# Hutschienenmoped-XL_2ETH.net
KiCad netlist of a schematic drawn in EAGLE
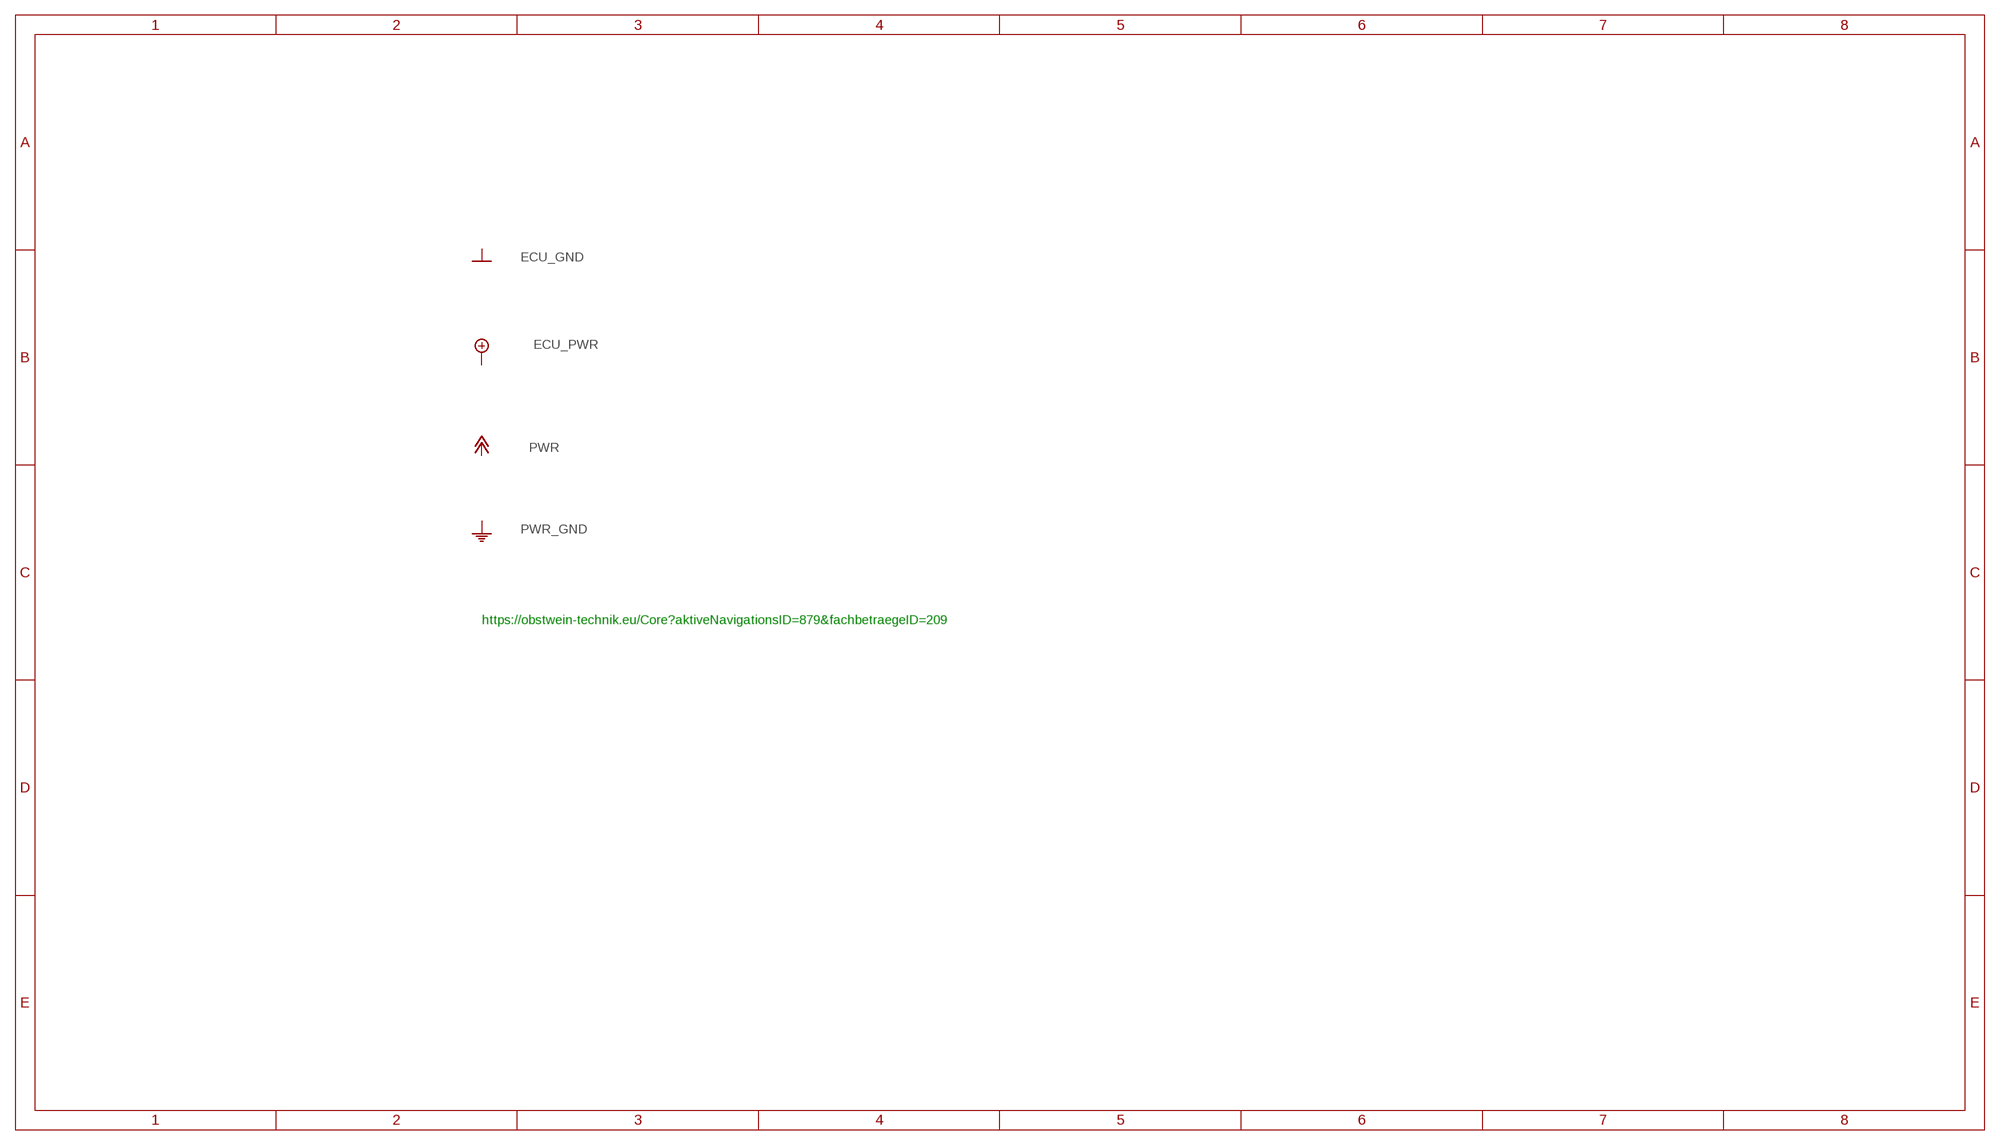
[diagram p0: schematic, sheet 1]
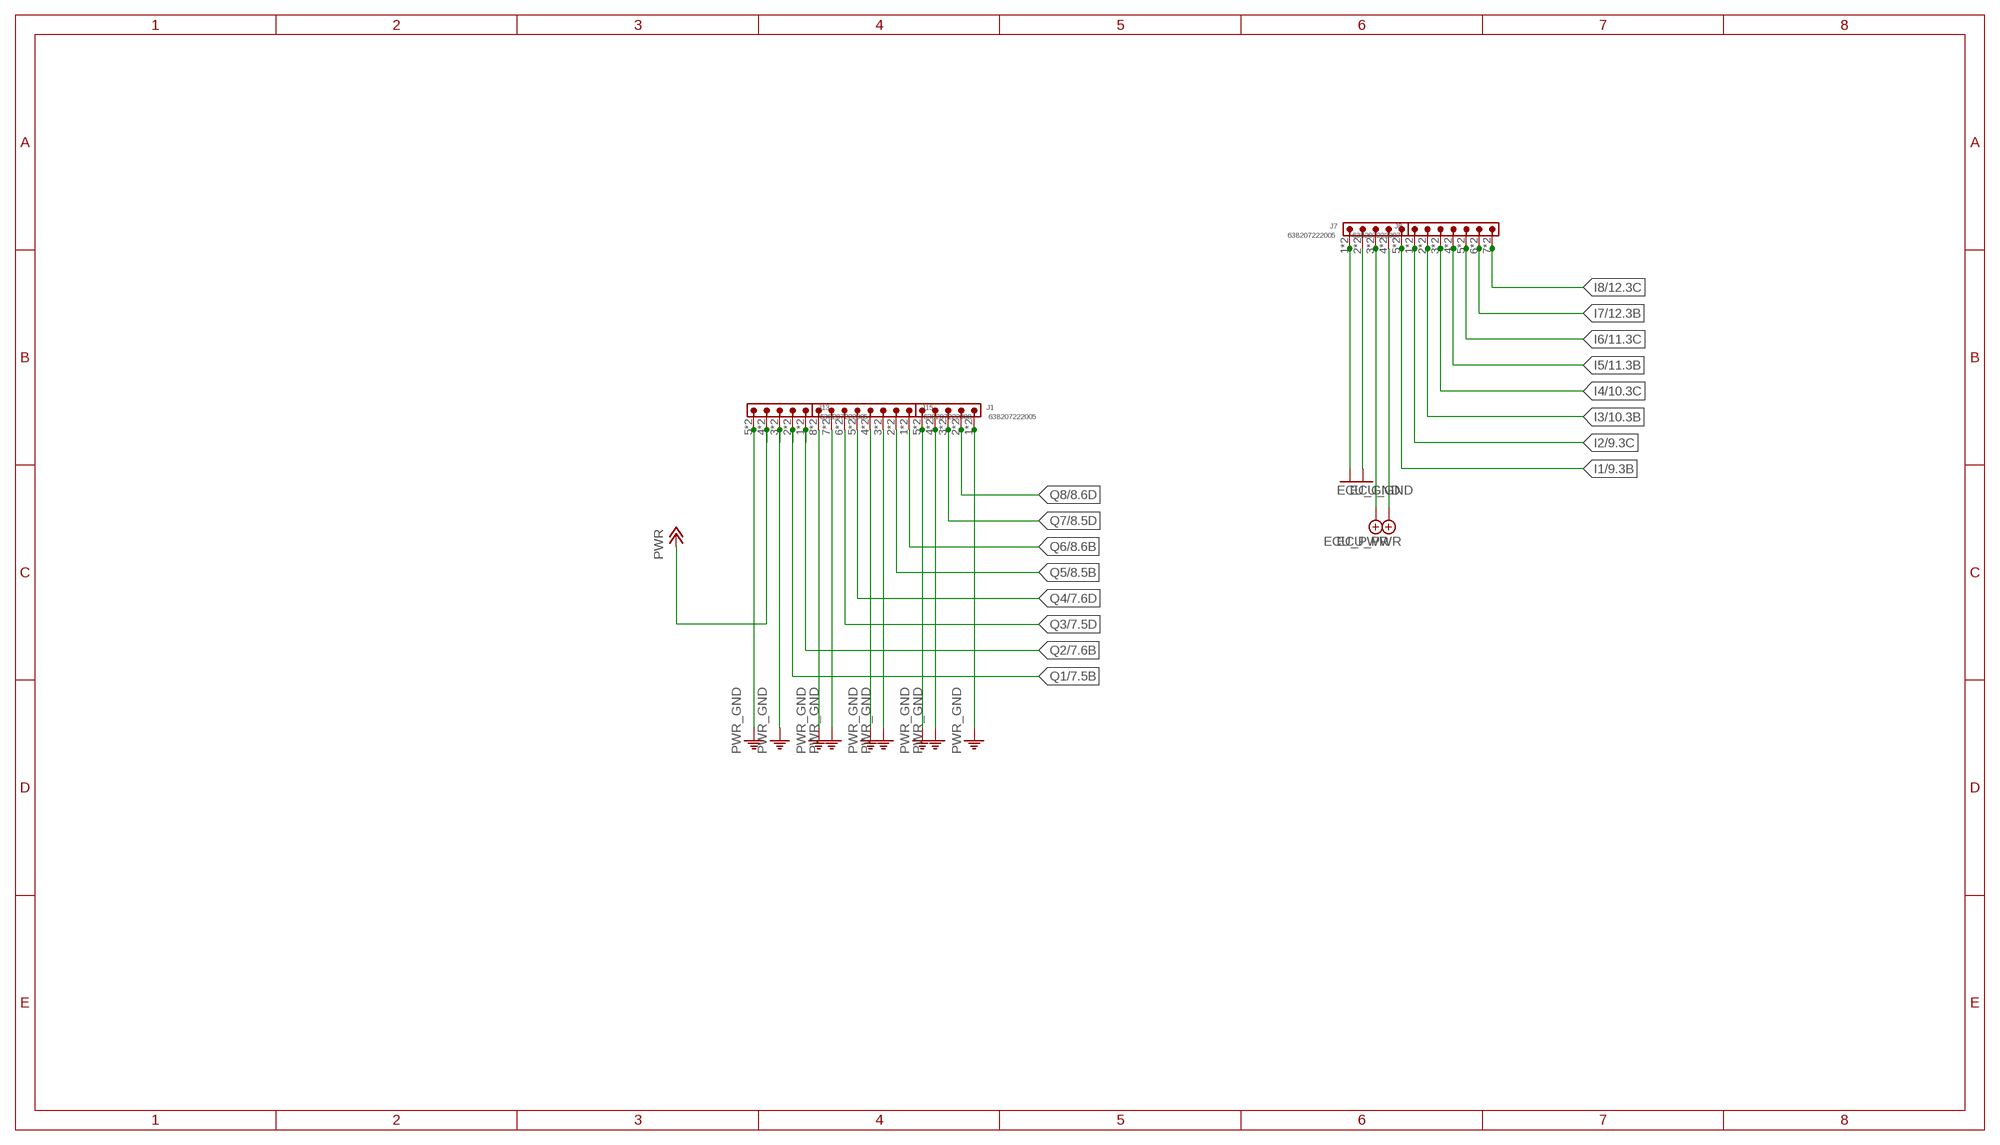
[diagram p1: schematic, sheet 2]
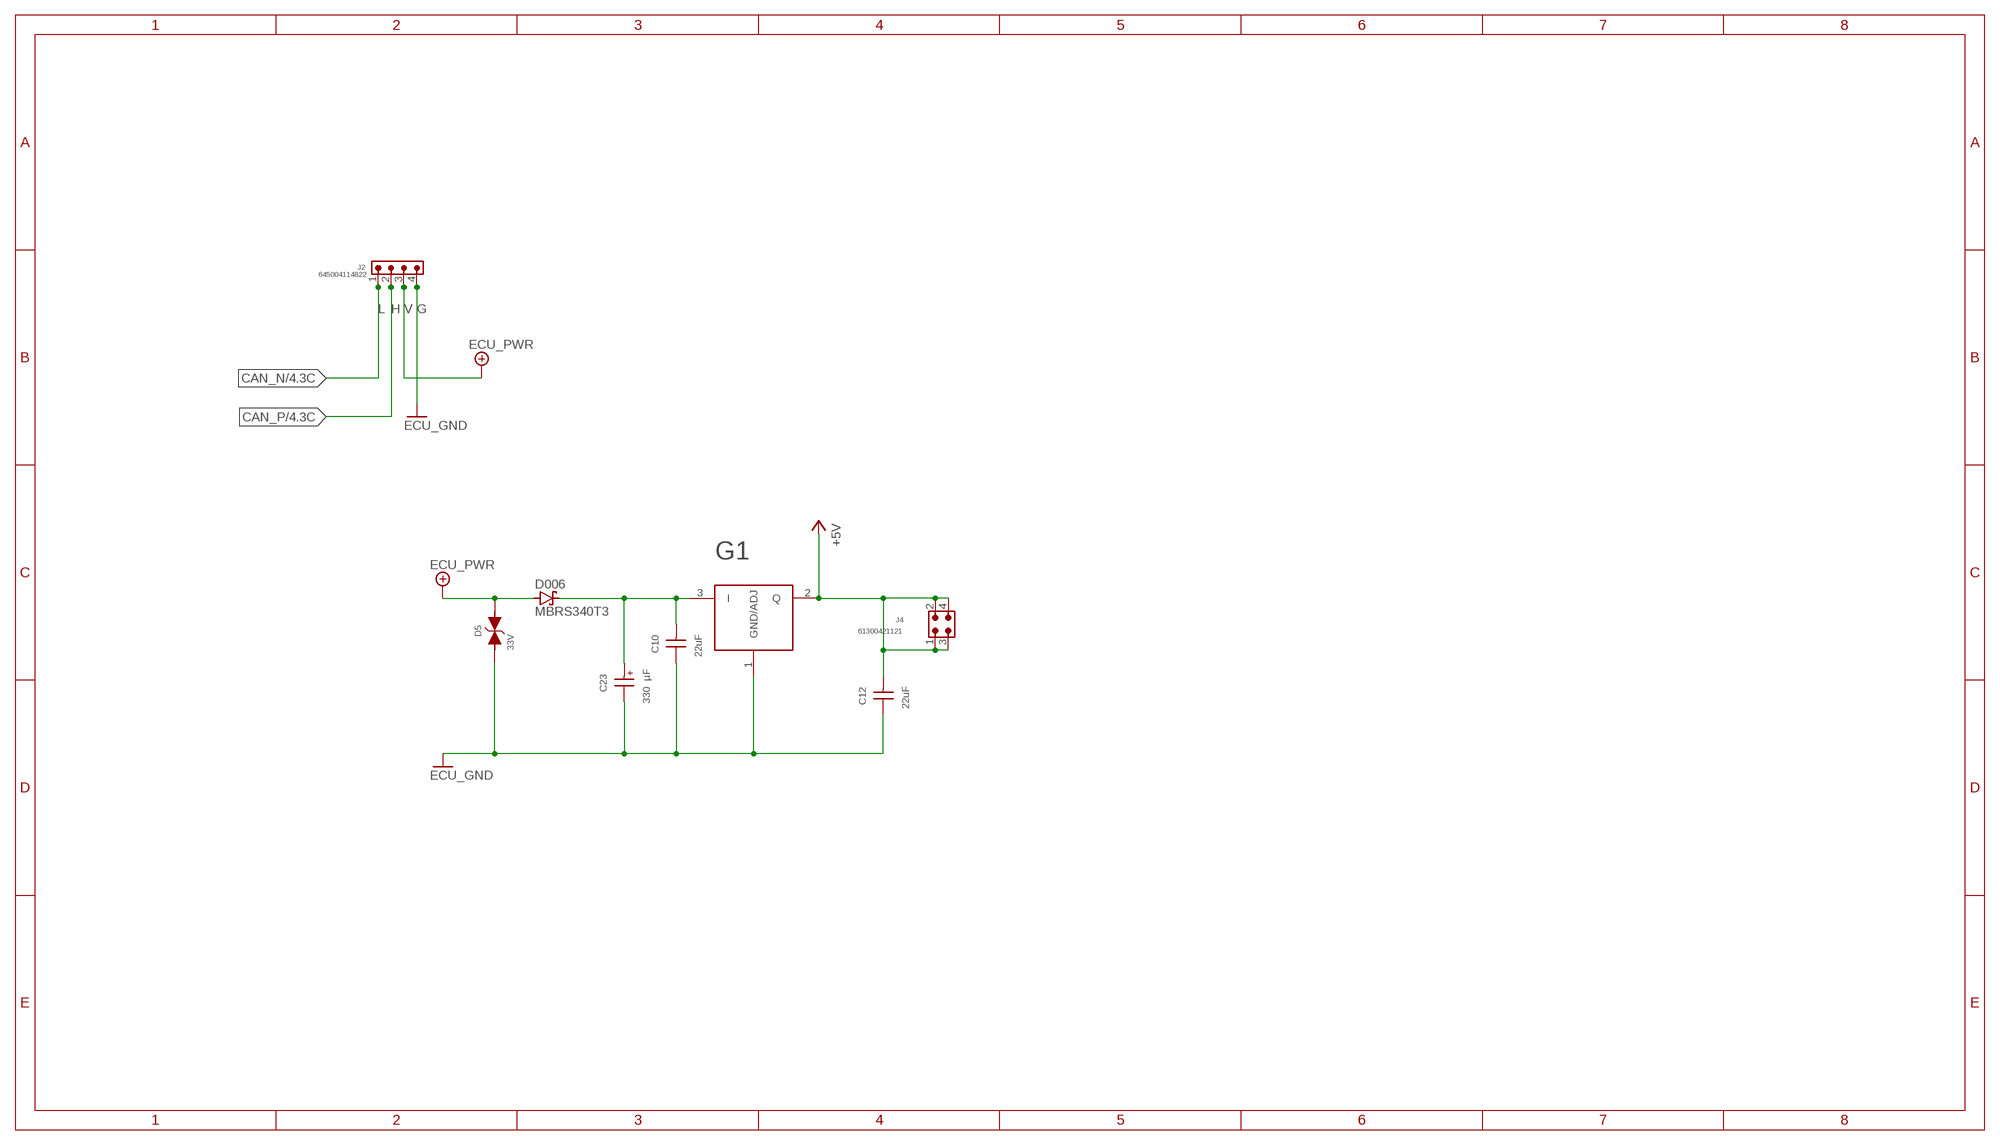
[diagram p2: schematic, sheet 3]
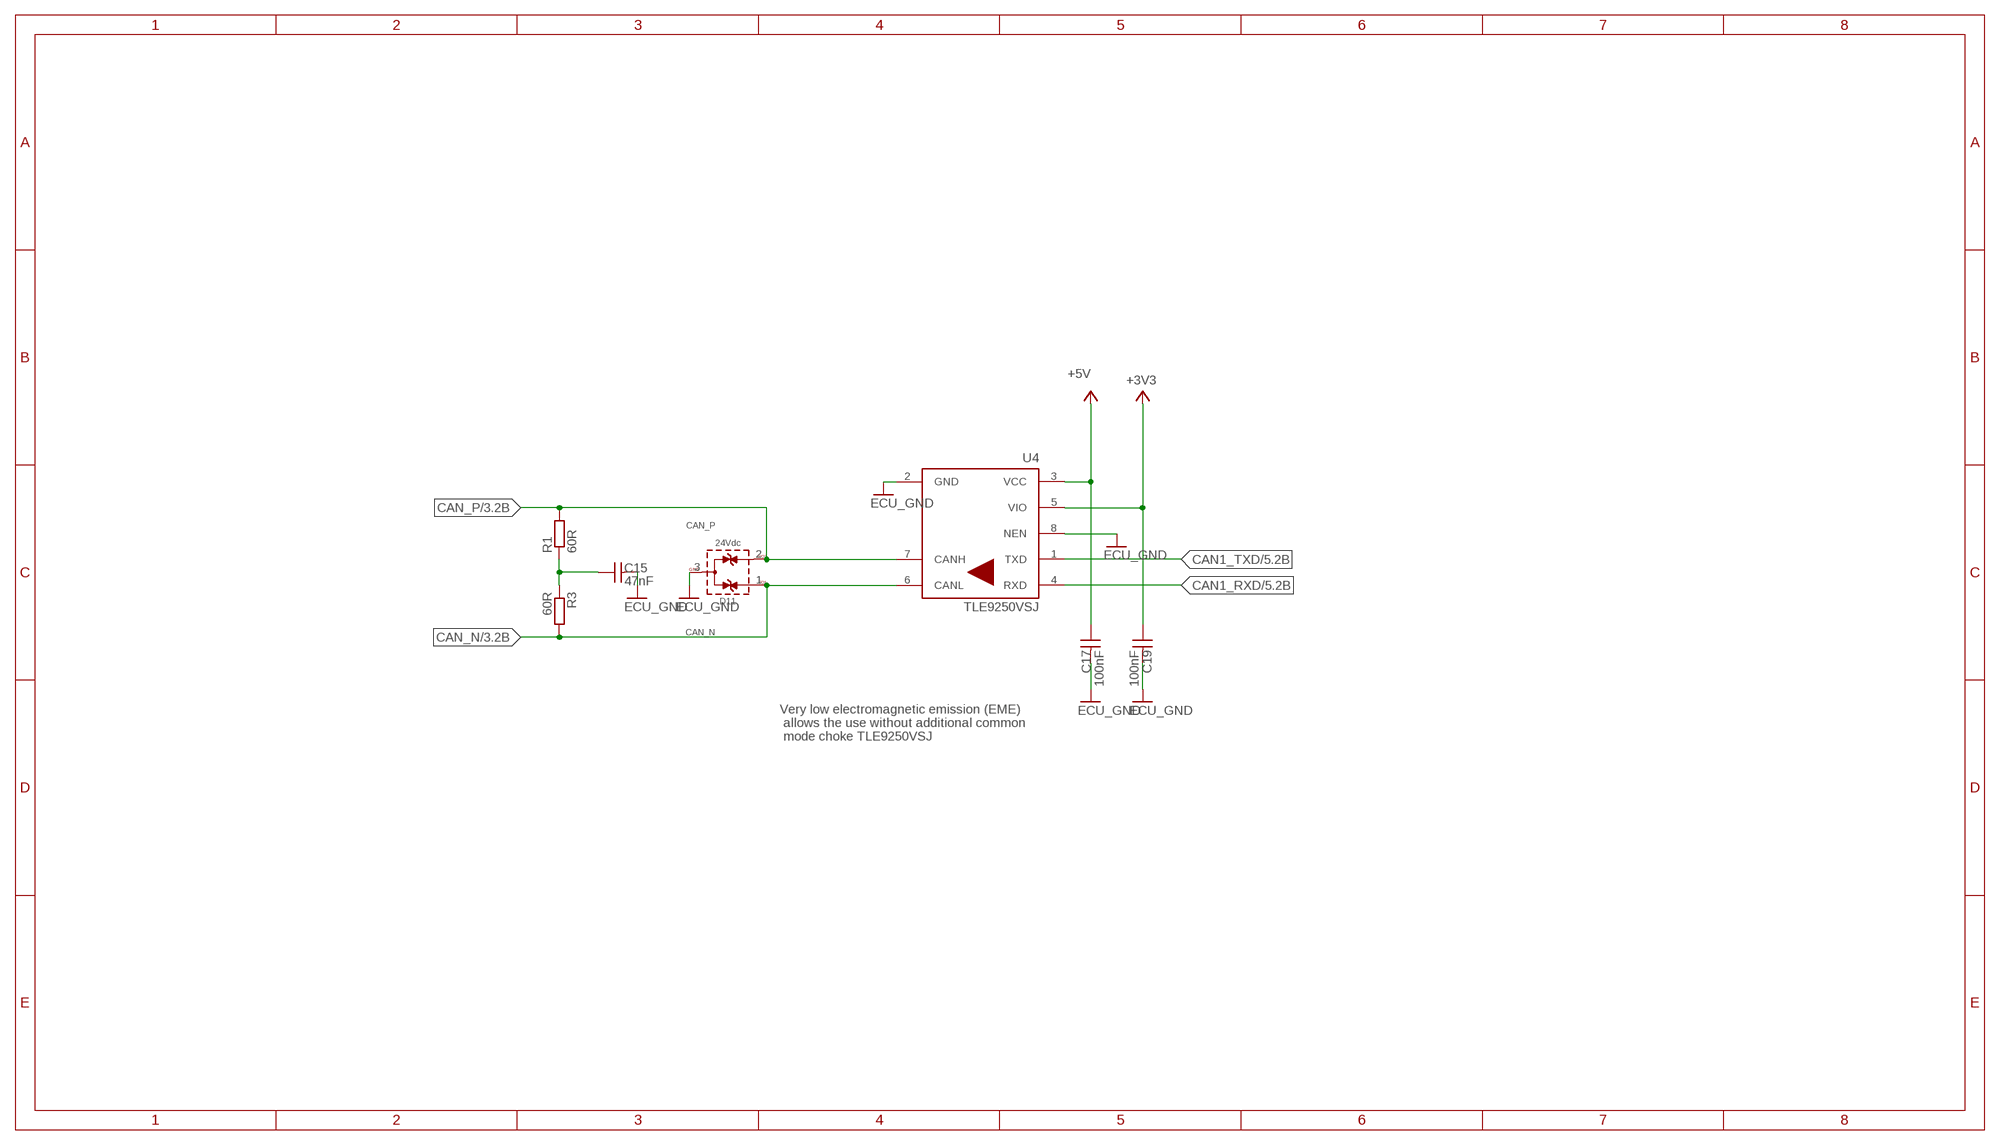
[diagram p3: schematic, sheet 4]
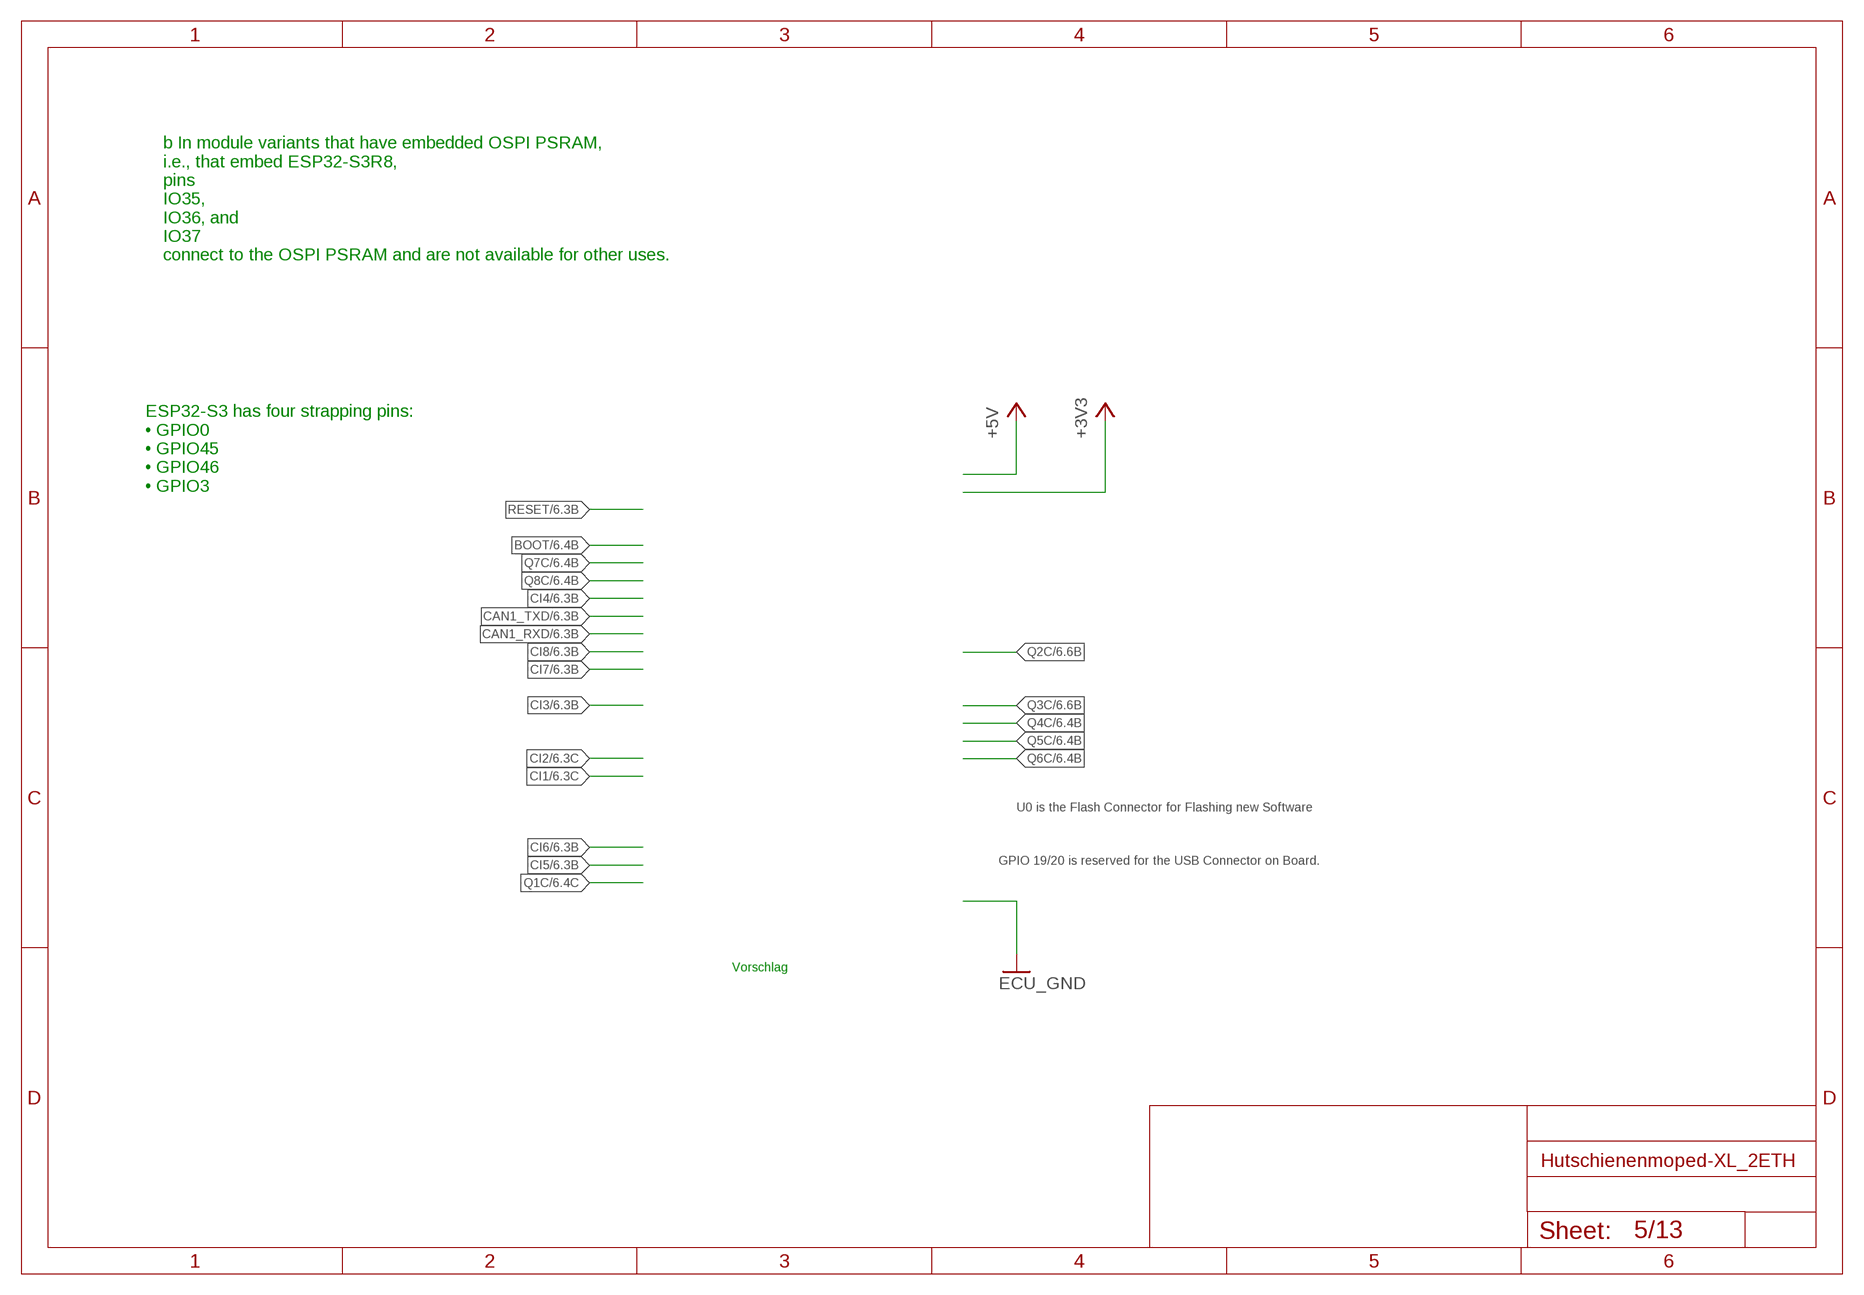
[diagram p4: schematic, sheet 5]
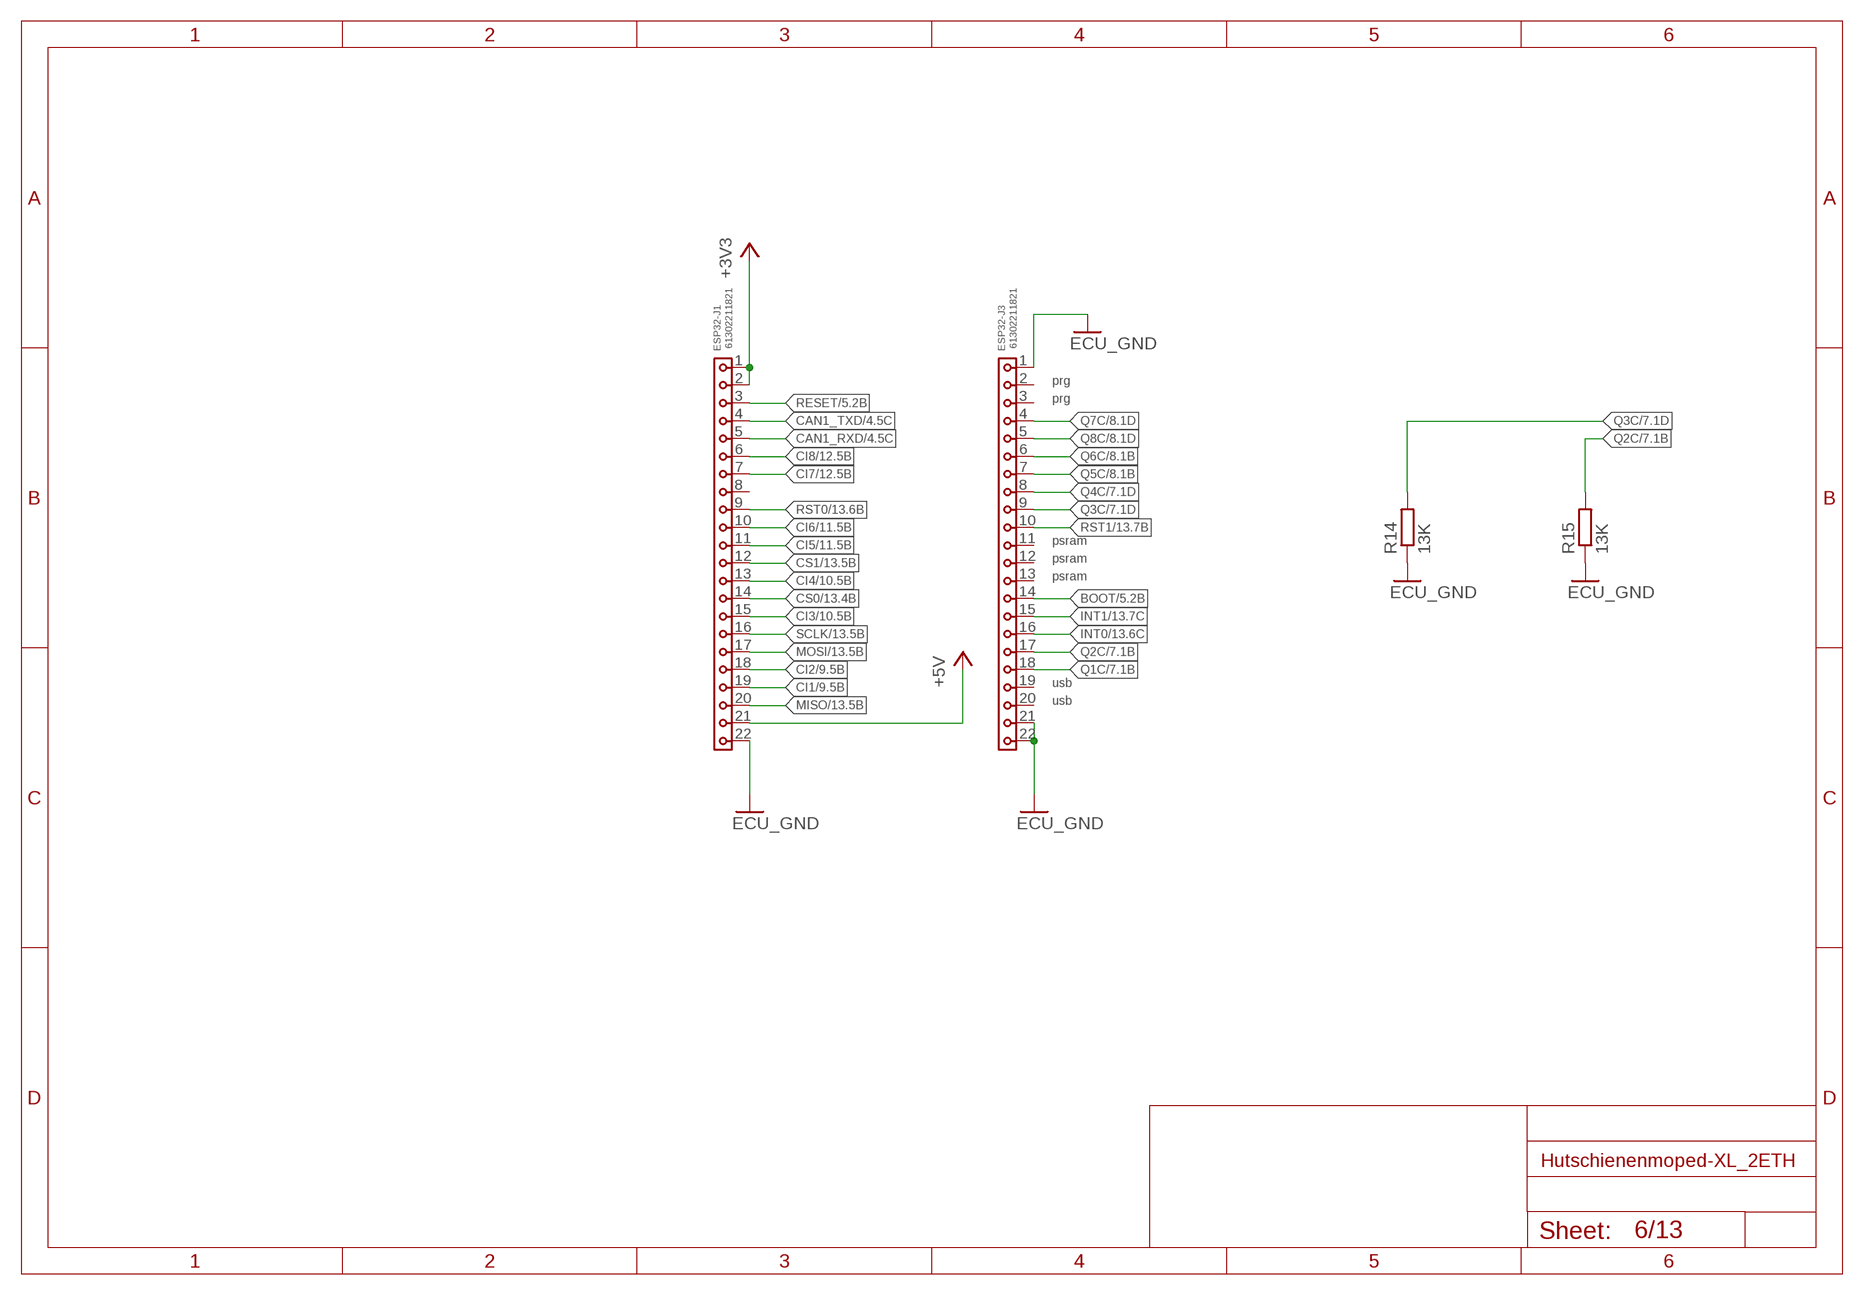
[diagram p5: schematic, sheet 6]
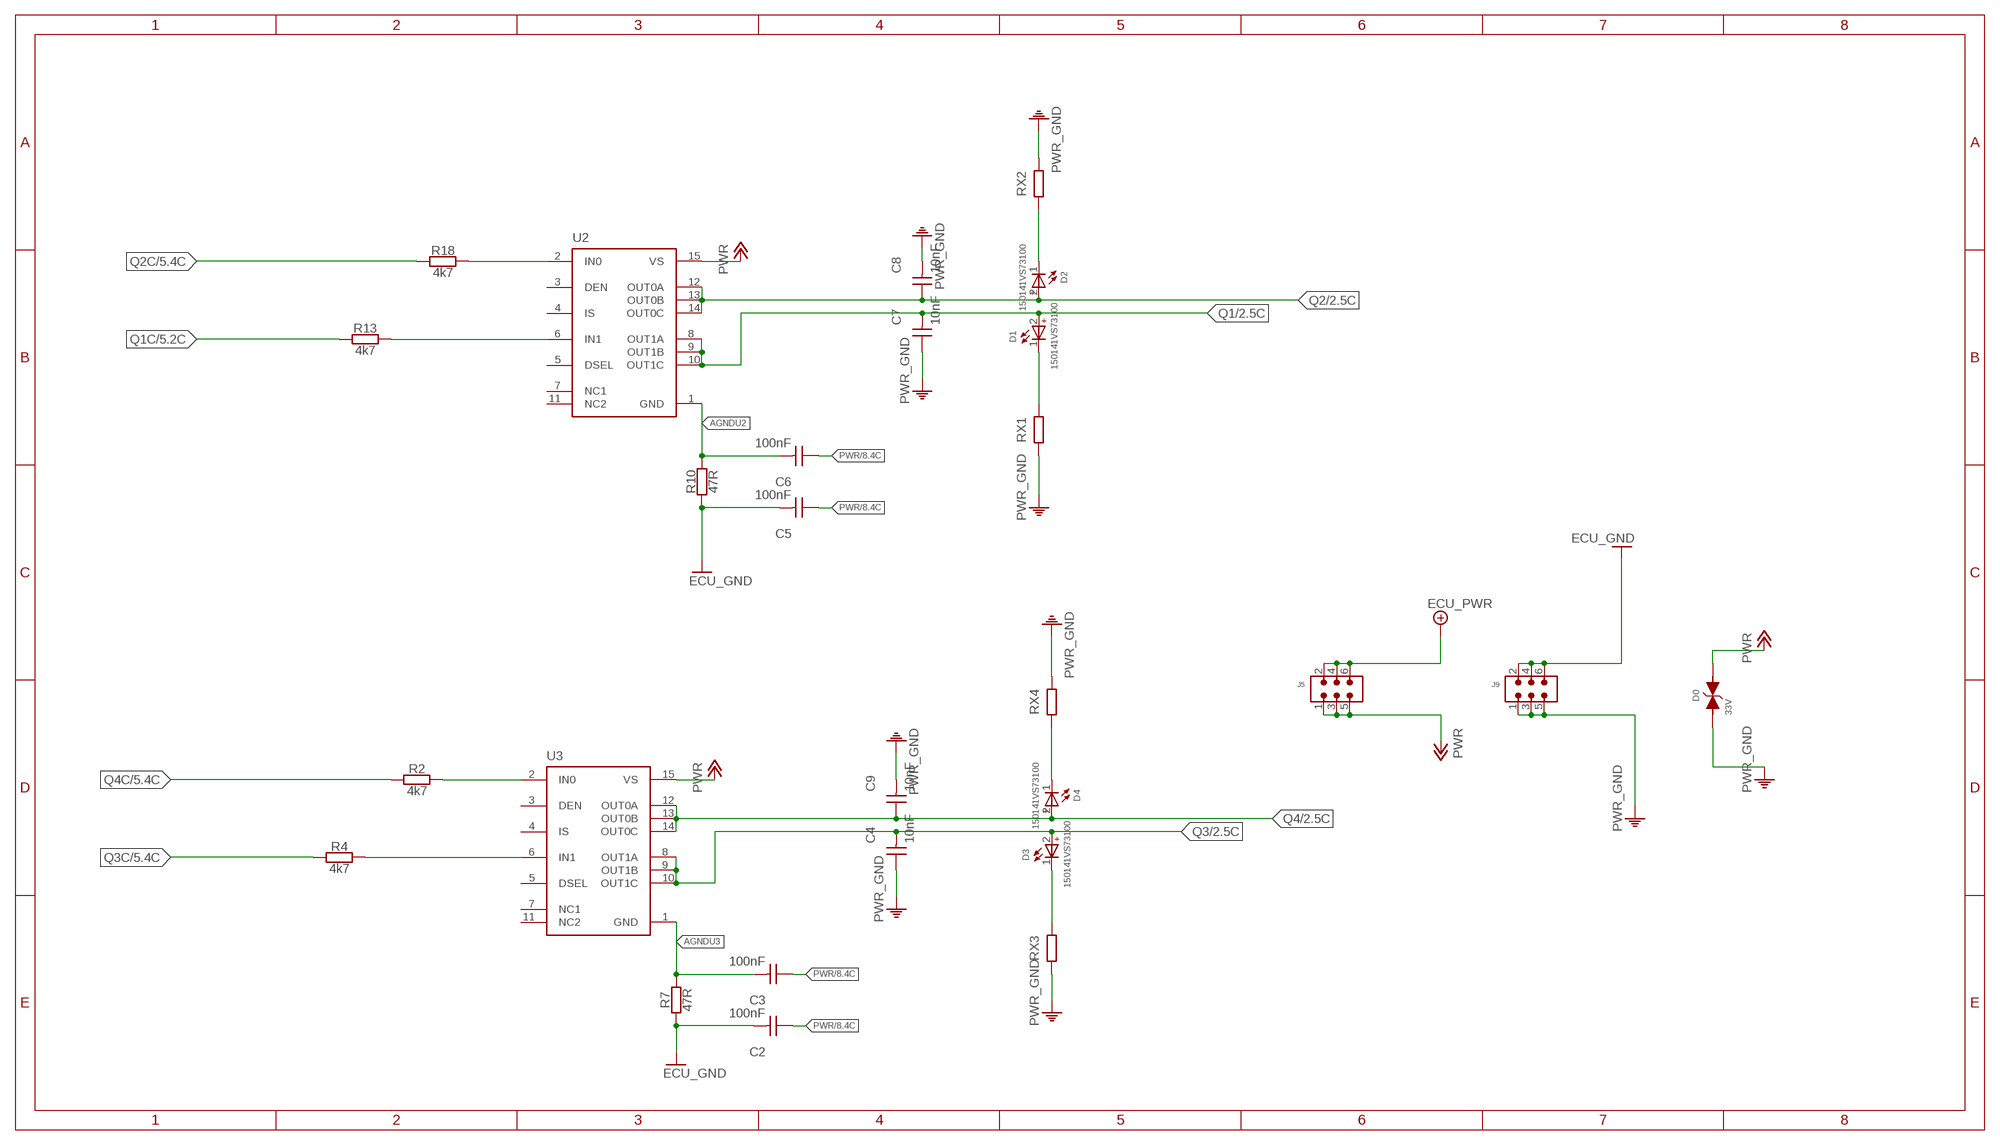
[diagram p6: schematic, sheet 7]
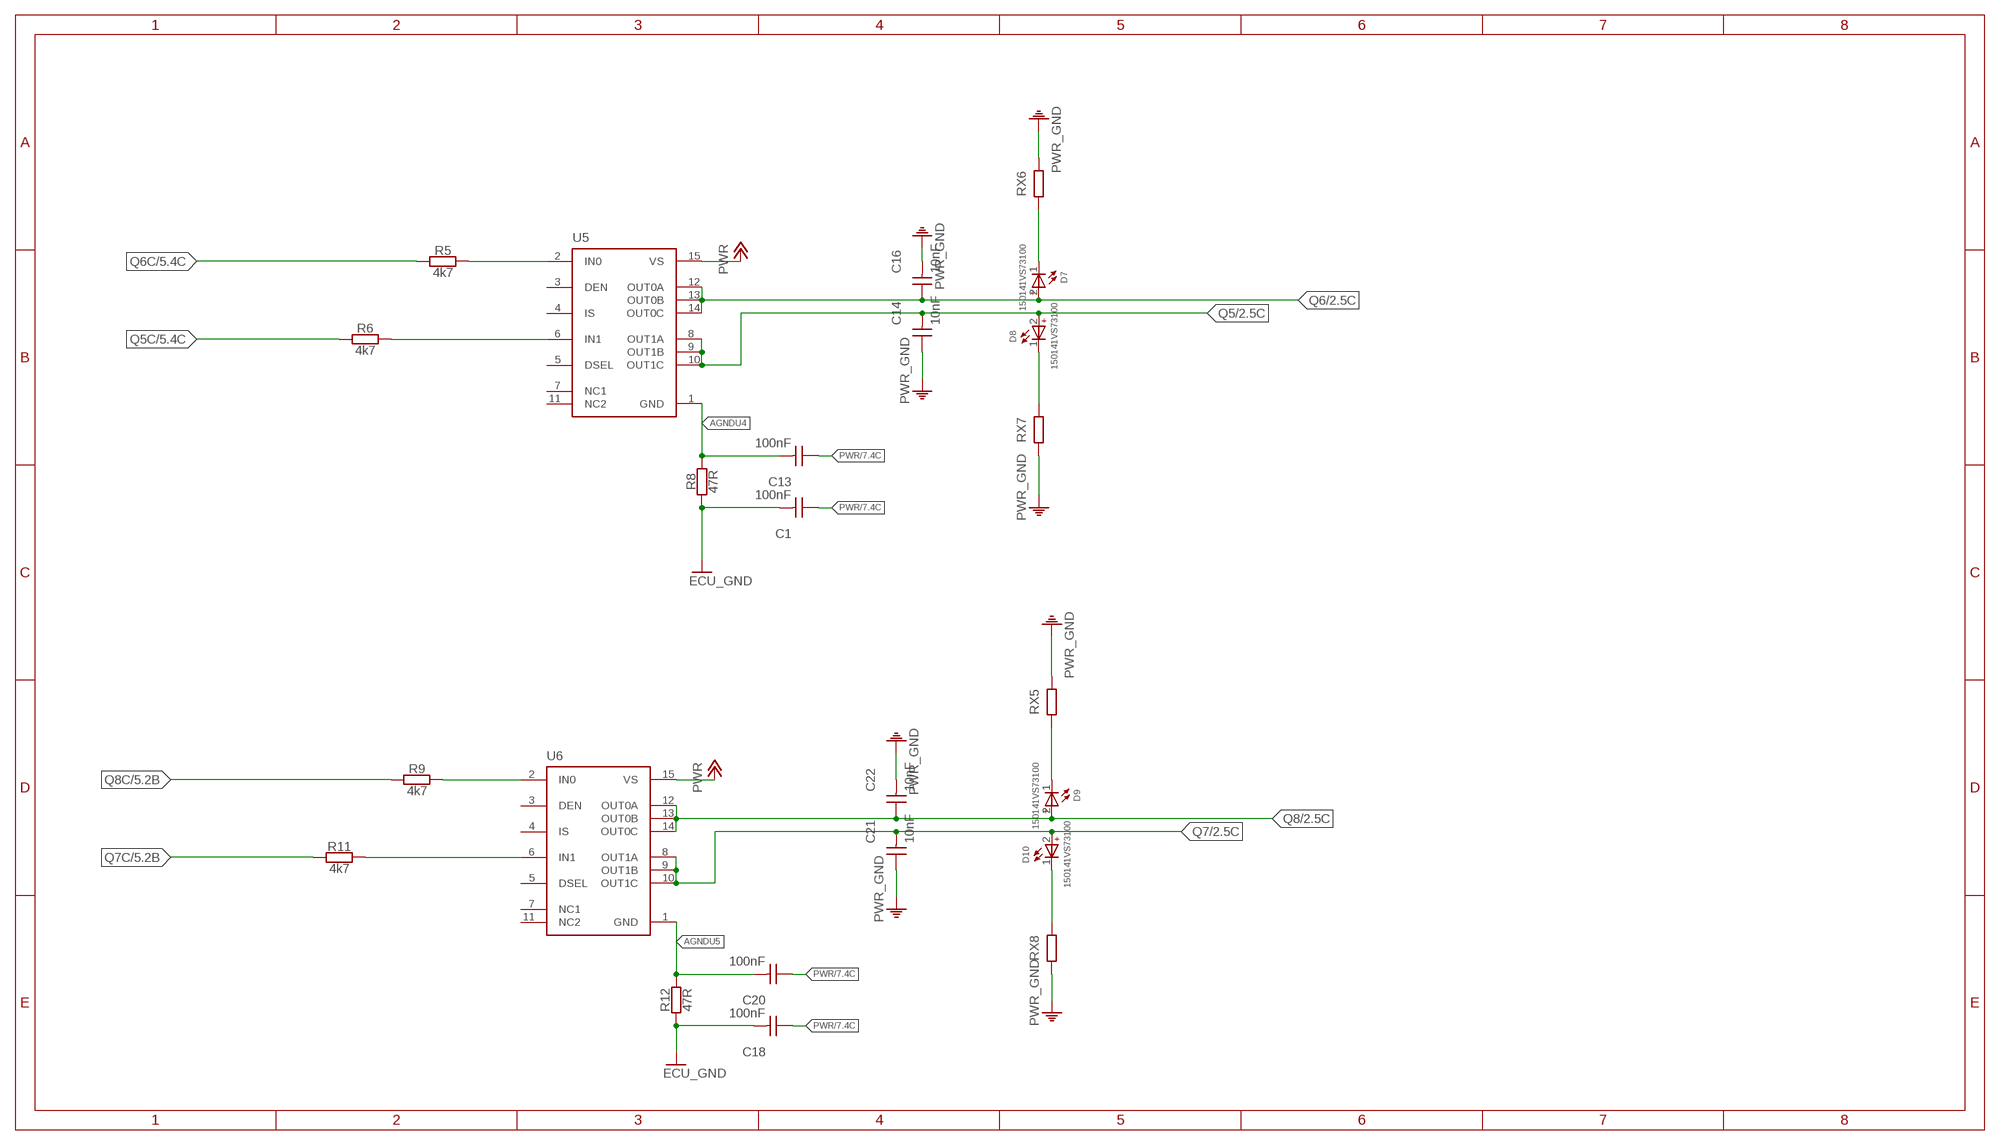
[diagram p7: schematic, sheet 8]
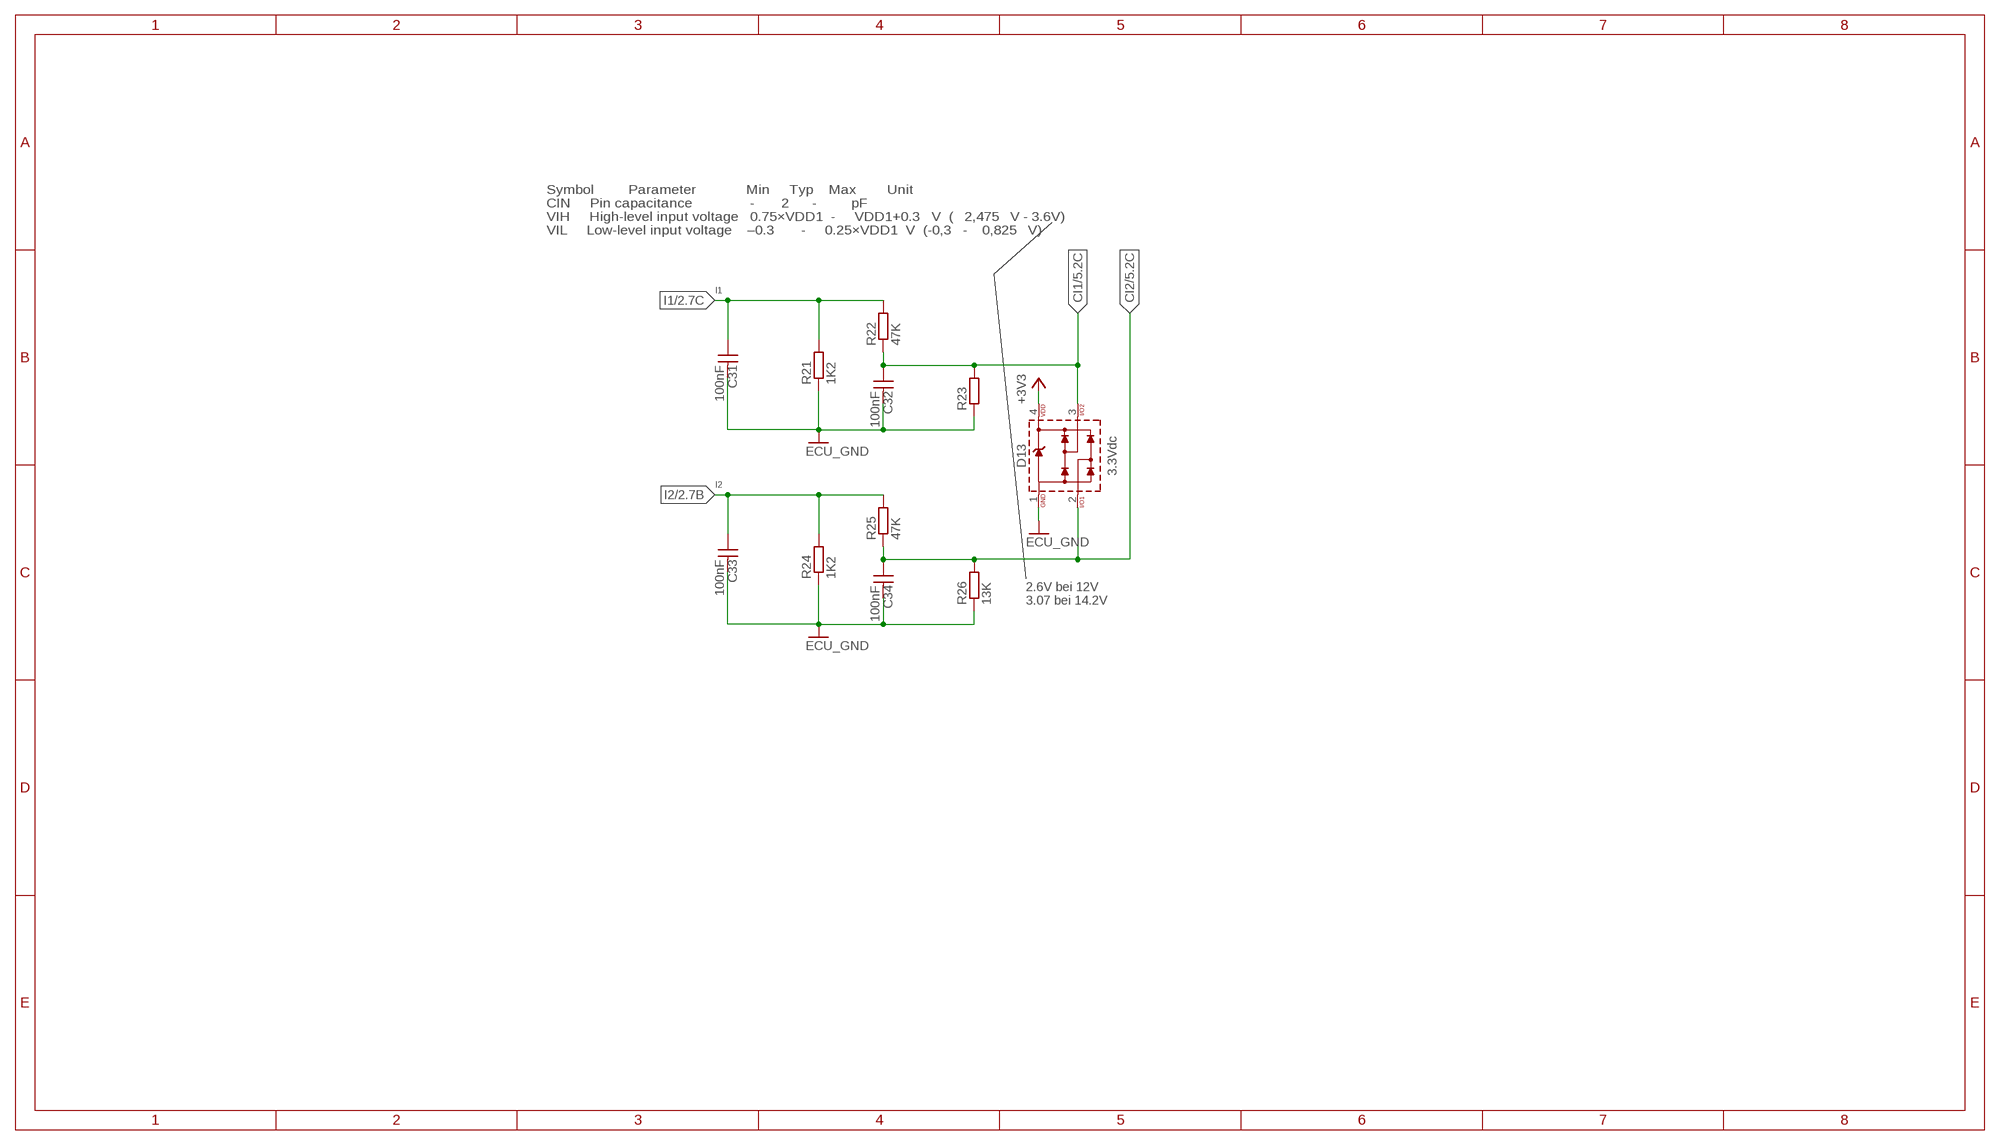
[diagram p8: schematic, sheet 9]
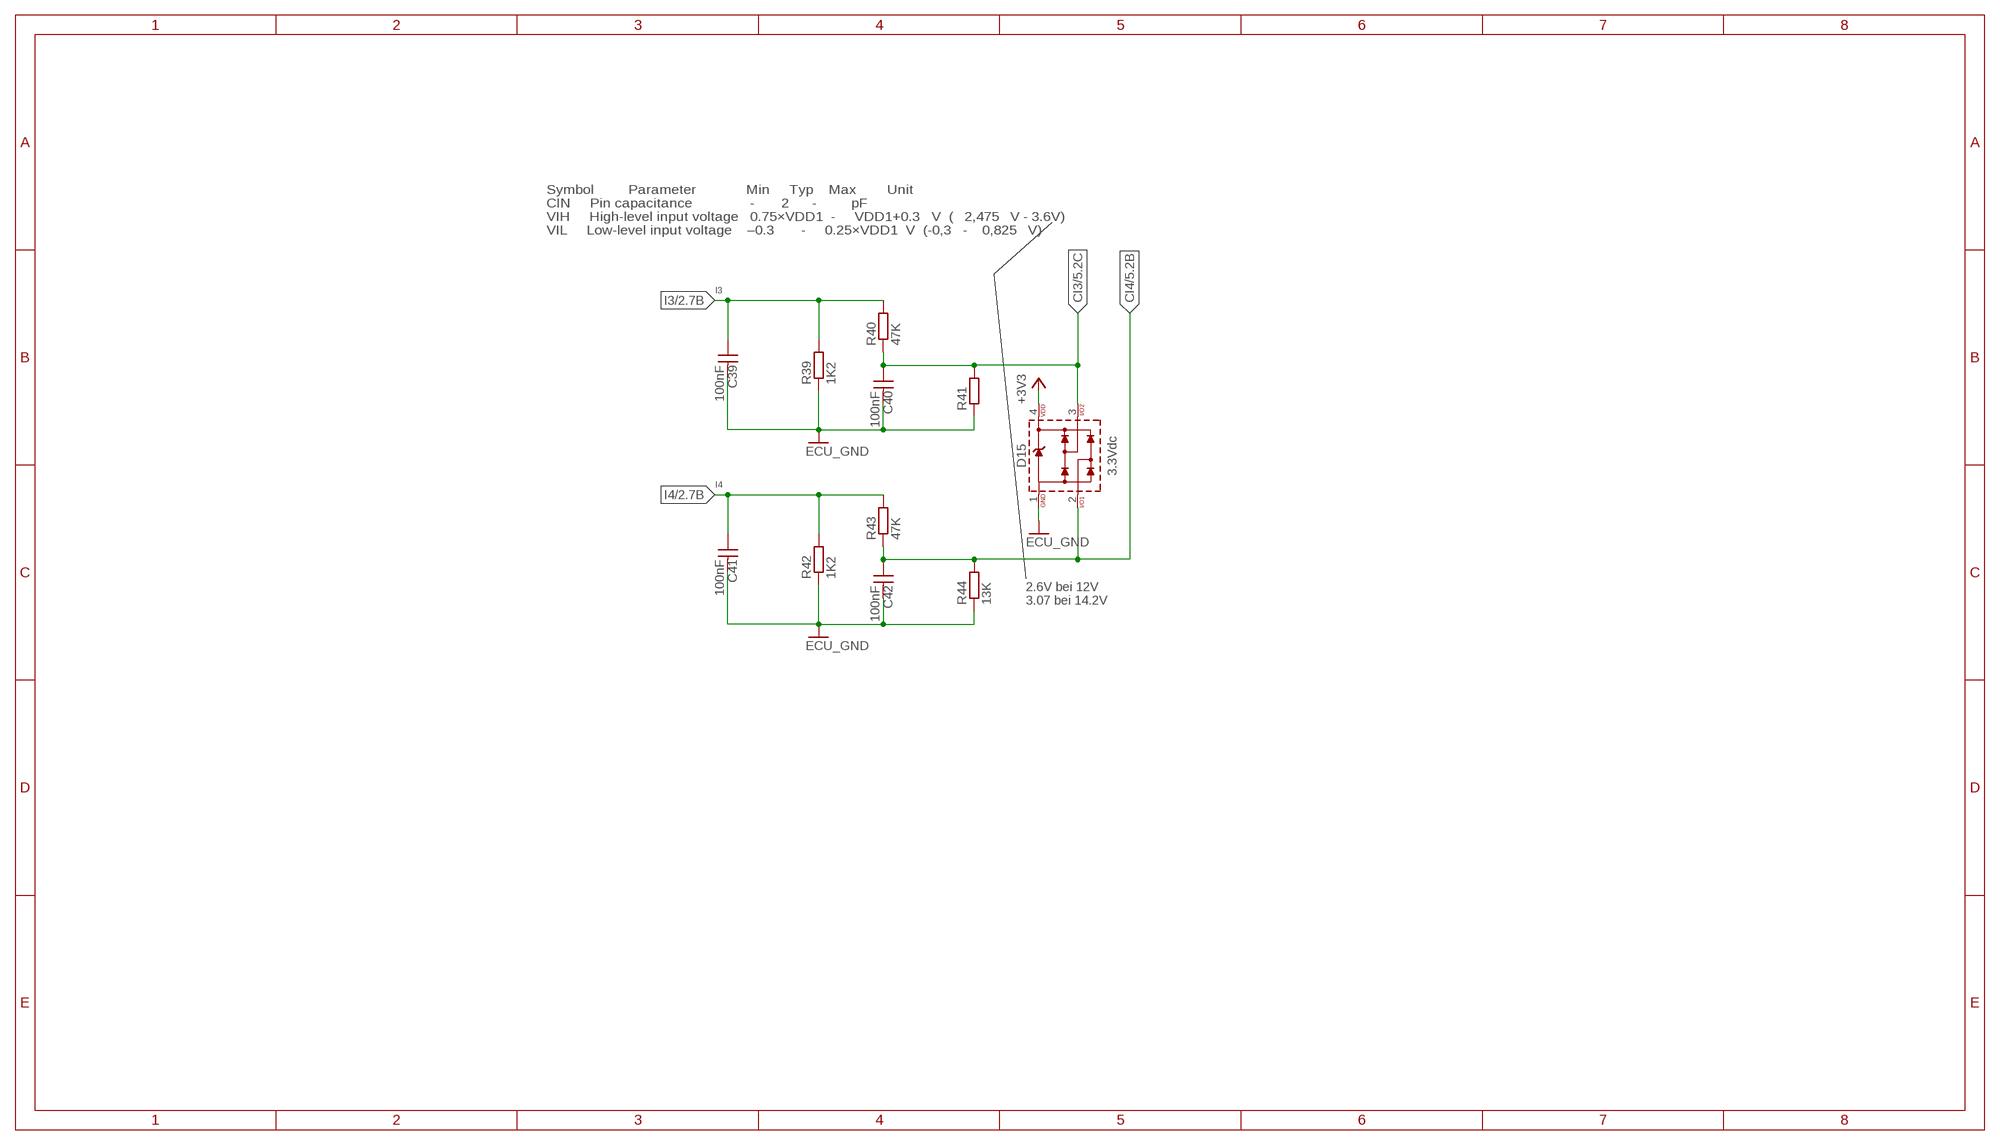
[diagram p9: schematic, sheet 10]
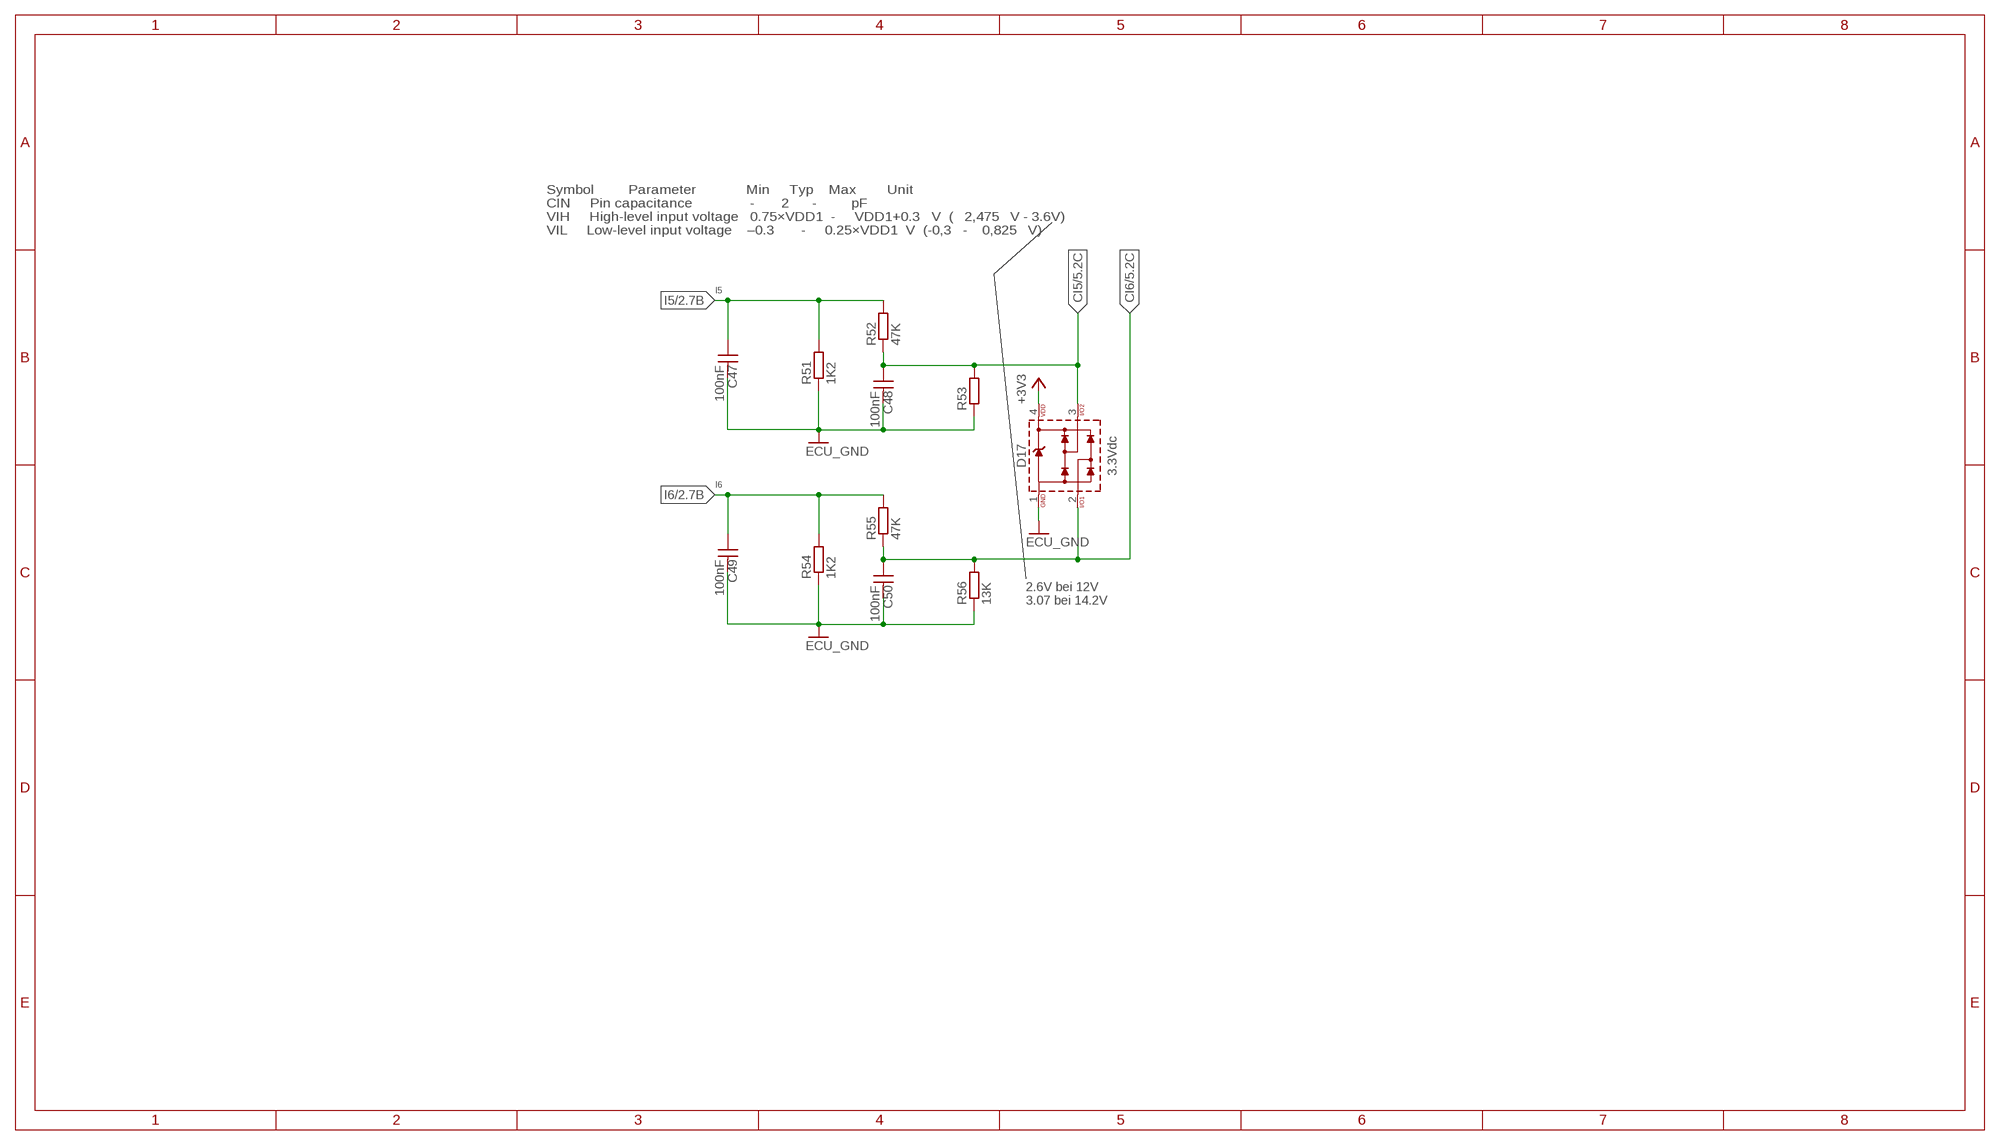
[diagram p10: schematic, sheet 11]
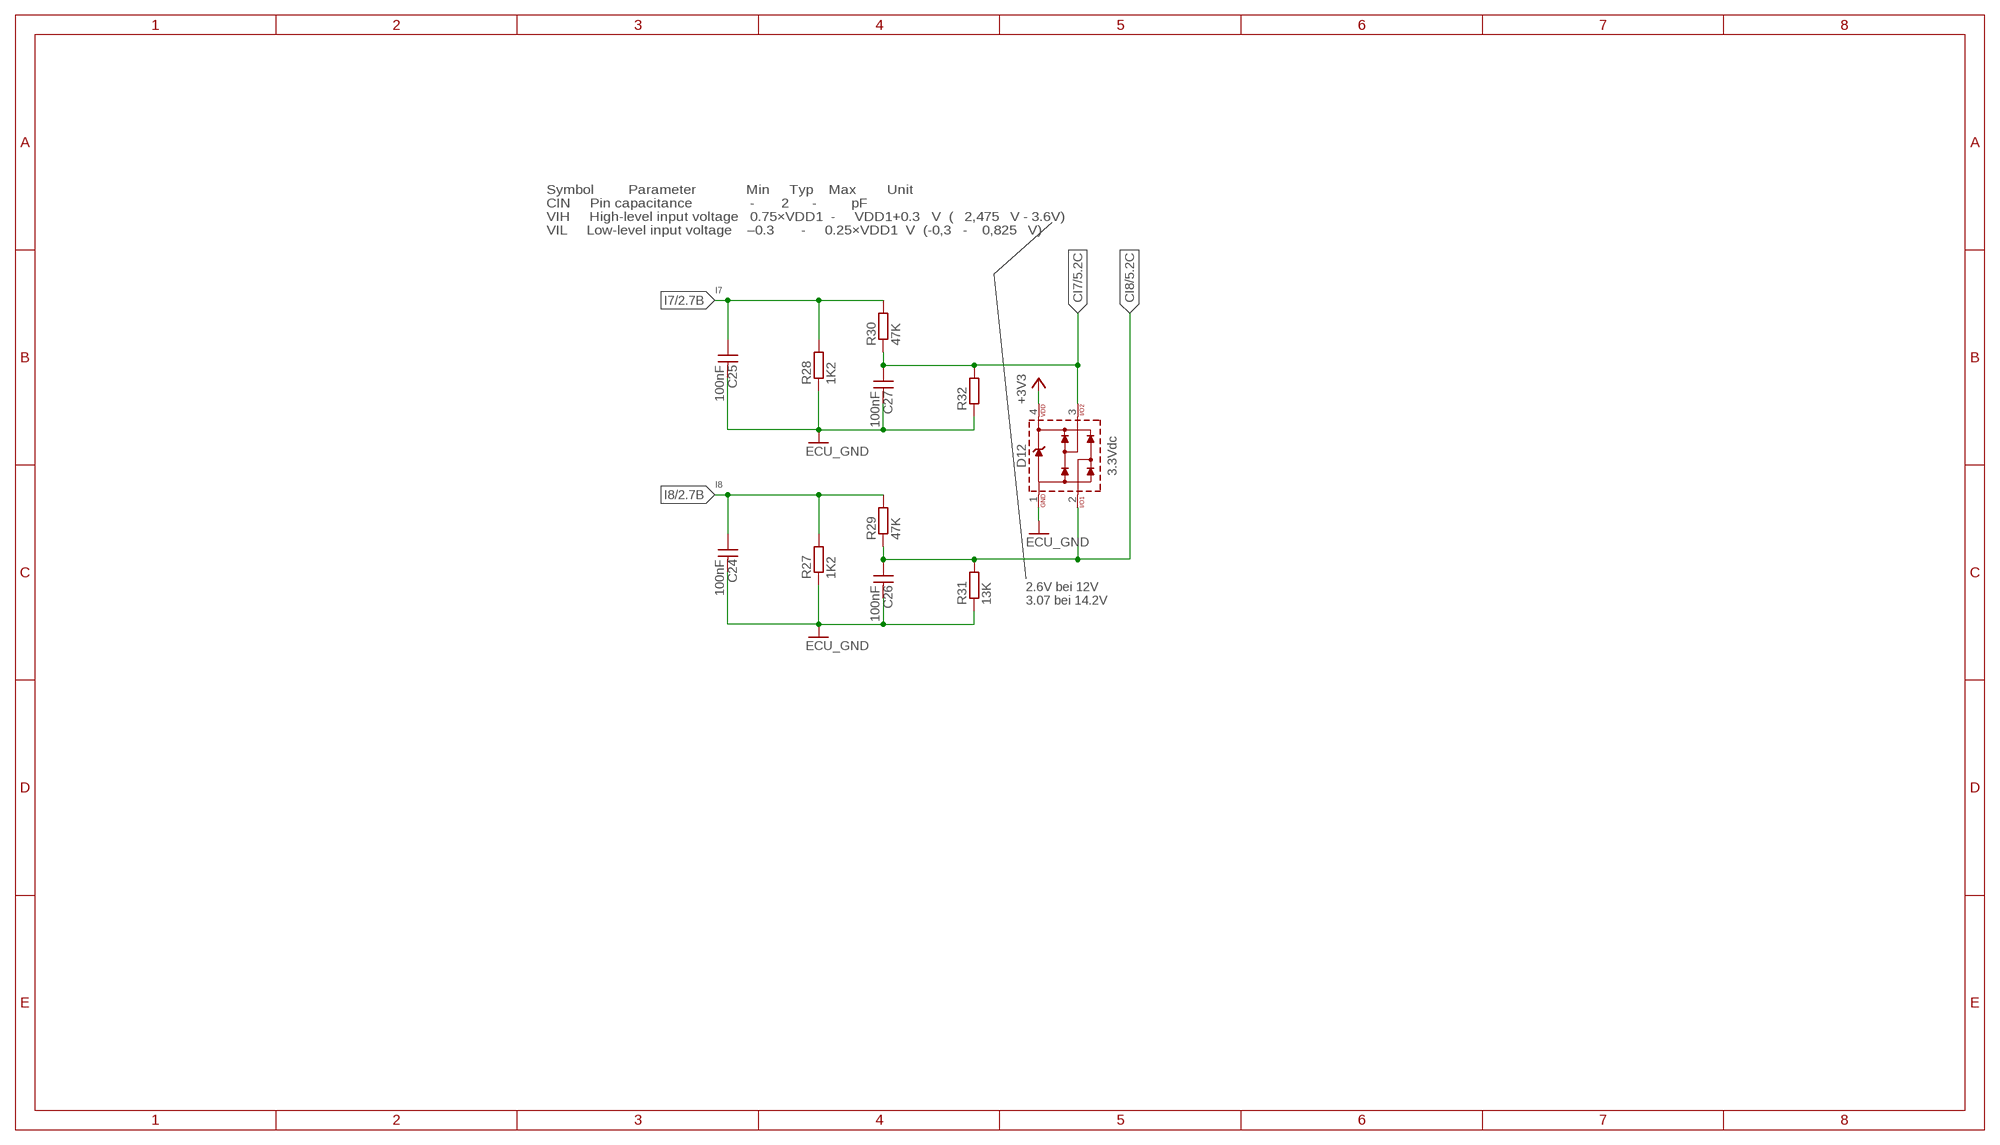
[diagram p11: schematic, sheet 12]
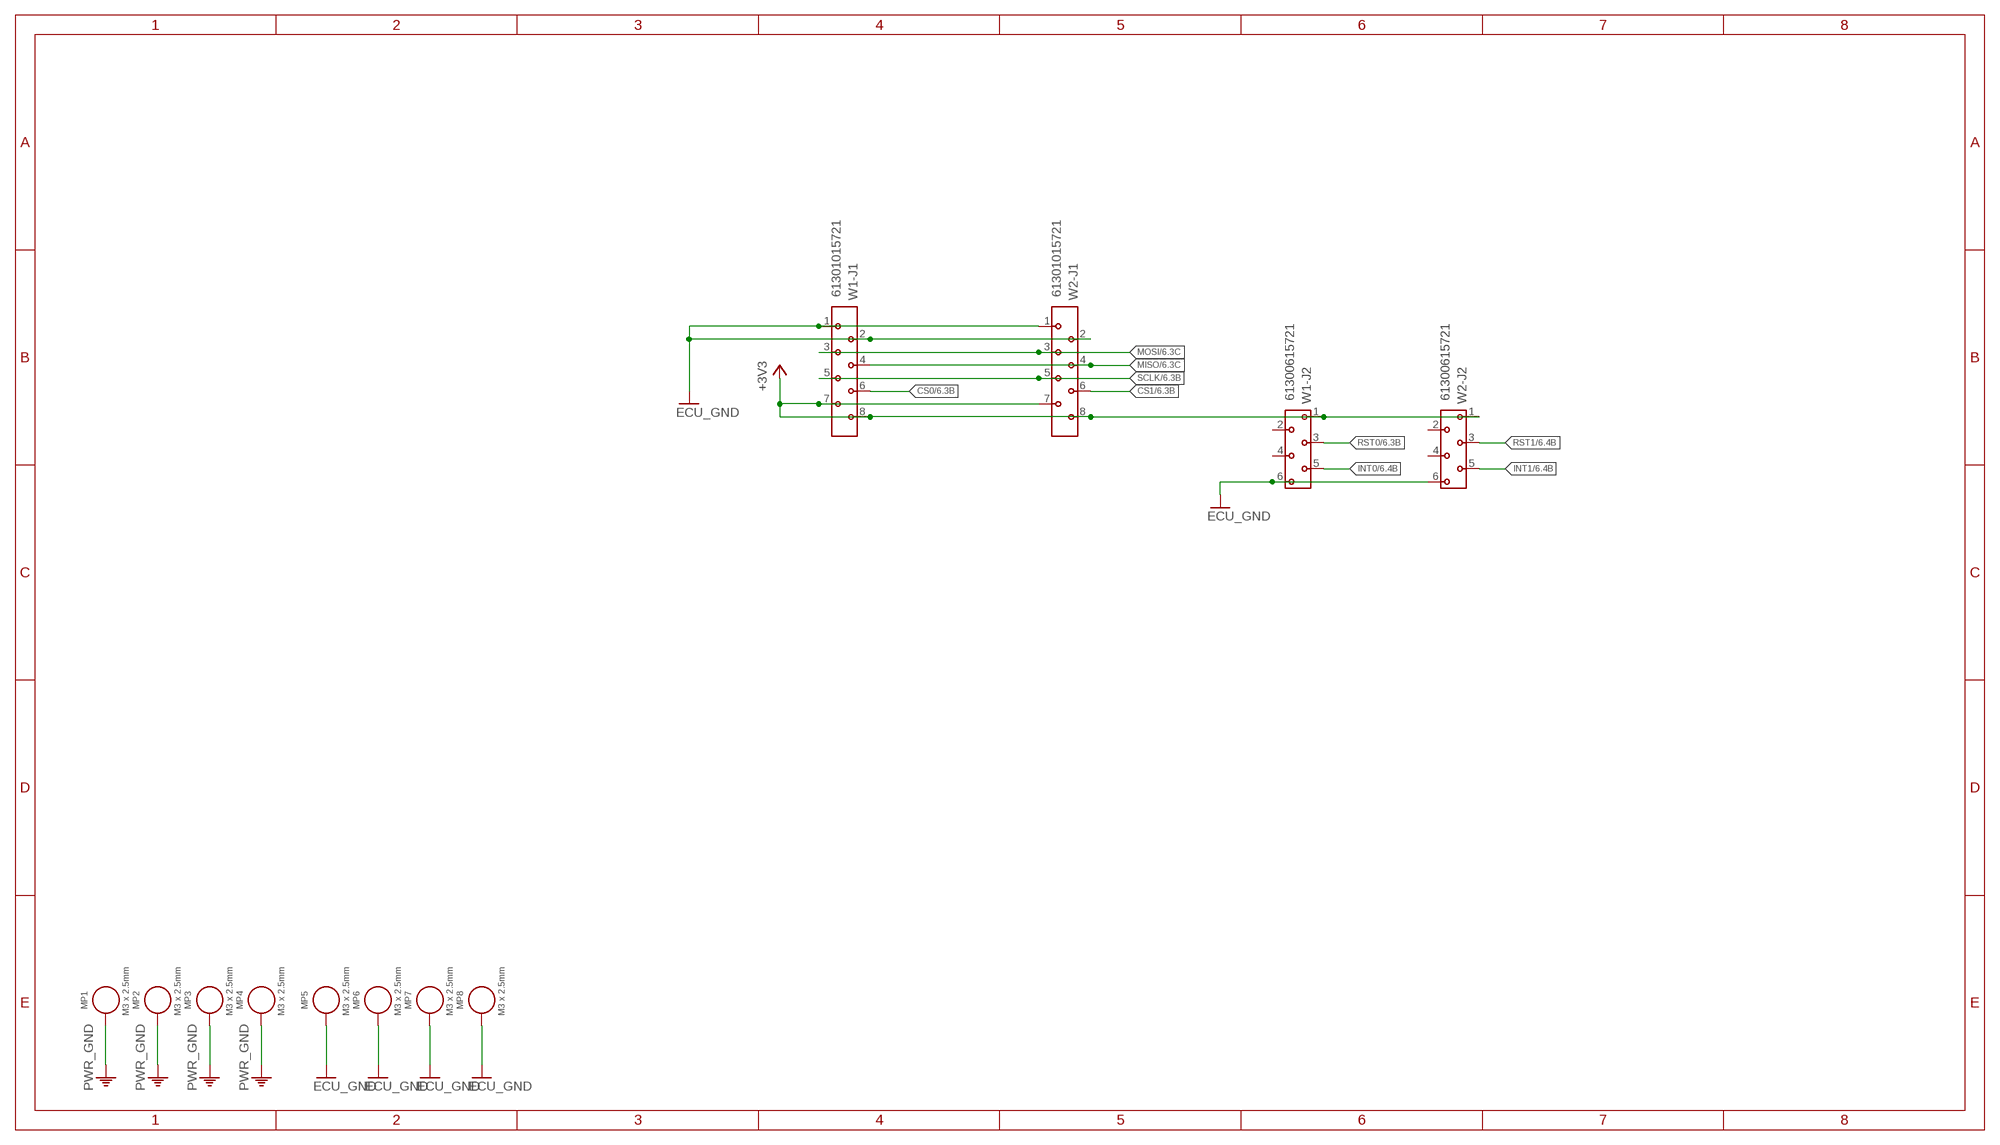
[diagram p12: schematic, sheet 13]

(export (version "E")
  (design (tool "Eeschema 10.0.6"))
  (components
    (comp (ref "C47")
      (value "100nF")
      (footprint "eagle-import:WCAP-CSGP_1206_H0.8")
      (libsource (lib "eagle-import") (part "WCAP-CSGP_1206_H0.8_50V(DC)_885012208087"))
    )
    (comp (ref "C48")
      (value "100nF")
      (footprint "eagle-import:WCAP-CSGP_1206_H0.8")
      (libsource (lib "eagle-import") (part "WCAP-CSGP_1206_H0.8_50V(DC)_885012208087"))
    )
    (comp (ref "C49")
      (value "100nF")
      (footprint "eagle-import:WCAP-CSGP_1206_H0.8")
      (libsource (lib "eagle-import") (part "WCAP-CSGP_1206_H0.8_50V(DC)_885012208087"))
    )
    (comp (ref "C50")
      (value "100nF")
      (footprint "eagle-import:WCAP-CSGP_1206_H0.8")
      (libsource (lib "eagle-import") (part "WCAP-CSGP_1206_H0.8_50V(DC)_885012208087"))
    )
    (comp (ref "D17")
      (value "3.3Vdc")
      (footprint "eagle-import:WE-TVS_SOT143-4L")
      (libsource (lib "eagle-import") (part "WE-TVS-HS_SOT143-4L_8240136"))
    )
    (comp (ref "R51")
      (value "1K2")
      (footprint "eagle-import:R1206")
      (libsource (lib "eagle-import") (part "R-EU_R1206"))
    )
    (comp (ref "R52")
      (value "47K")
      (footprint "eagle-import:R1206")
      (libsource (lib "eagle-import") (part "R-EU_R1206"))
    )
    (comp (ref "R53")
      (value "13K")
      (footprint "eagle-import:R1206")
      (libsource (lib "eagle-import") (part "R-EU_R1206"))
    )
    (comp (ref "R54")
      (value "1K2")
      (footprint "eagle-import:R1206")
      (libsource (lib "eagle-import") (part "R-EU_R1206"))
    )
    (comp (ref "R55")
      (value "47K")
      (footprint "eagle-import:R1206")
      (libsource (lib "eagle-import") (part "R-EU_R1206"))
    )
    (comp (ref "R56")
      (value "13K")
      (footprint "eagle-import:R1206")
      (libsource (lib "eagle-import") (part "R-EU_R1206"))
    )
    (comp (ref "C15")
      (value "47nF")
      (footprint "eagle-import:WCAP-CSGP_0805_H0.8_R")
      (libsource (lib "eagle-import") (part "WCAP-CSGP_0805_H0.8_50V(DC)_R_885012207096"))
    )
    (comp (ref "C17")
      (value "100nF")
      (footprint "eagle-import:WCAP-CSGP_0805_H0.8_R")
      (libsource (lib "eagle-import") (part "WCAP-CSGP_0805_H0.8_50V(DC)_R_885012207098"))
    )
    (comp (ref "C19")
      (value "100nF")
      (footprint "eagle-import:WCAP-CSGP_0805_H0.8_R")
      (libsource (lib "eagle-import") (part "WCAP-CSGP_0805_H0.8_50V(DC)_R_885012207098"))
    )
    (comp (ref "D11")
      (value "24Vdc")
      (footprint "eagle-import:WE-TVS_SOT23-3L")
      (libsource (lib "eagle-import") (part "WE-TVS_SOT23-3L_824094024"))
    )
    (comp (ref "R1")
      (value "60R")
      (footprint "eagle-import:R0805")
      (libsource (lib "eagle-import") (part "R-EU_R0805"))
    )
    (comp (ref "R3")
      (value "60R")
      (footprint "eagle-import:R0805")
      (libsource (lib "eagle-import") (part "R-EU_R0805"))
    )
    (comp (ref "U4")
      (value "TLE9250VSJ")
      (footprint "eagle-import:SOIC127P602X173-8N-V")
      (libsource (lib "eagle-import") (part "TLE9250VSJ"))
    )
    (comp (ref "C24")
      (value "100nF")
      (footprint "eagle-import:WCAP-CSGP_1206_H0.8")
      (libsource (lib "eagle-import") (part "WCAP-CSGP_1206_H0.8_50V(DC)_885012208087"))
    )
    (comp (ref "C25")
      (value "100nF")
      (footprint "eagle-import:WCAP-CSGP_1206_H0.8")
      (libsource (lib "eagle-import") (part "WCAP-CSGP_1206_H0.8_50V(DC)_885012208087"))
    )
    (comp (ref "C26")
      (value "100nF")
      (footprint "eagle-import:WCAP-CSGP_1206_H0.8")
      (libsource (lib "eagle-import") (part "WCAP-CSGP_1206_H0.8_50V(DC)_885012208087"))
    )
    (comp (ref "C27")
      (value "100nF")
      (footprint "eagle-import:WCAP-CSGP_1206_H0.8")
      (libsource (lib "eagle-import") (part "WCAP-CSGP_1206_H0.8_50V(DC)_885012208087"))
    )
    (comp (ref "D12")
      (value "3.3Vdc")
      (footprint "eagle-import:WE-TVS_SOT143-4L")
      (libsource (lib "eagle-import") (part "WE-TVS-HS_SOT143-4L_8240136"))
    )
    (comp (ref "R27")
      (value "1K2")
      (footprint "eagle-import:R1206")
      (libsource (lib "eagle-import") (part "R-EU_R1206"))
    )
    (comp (ref "R28")
      (value "1K2")
      (footprint "eagle-import:R1206")
      (libsource (lib "eagle-import") (part "R-EU_R1206"))
    )
    (comp (ref "R29")
      (value "47K")
      (footprint "eagle-import:R1206")
      (libsource (lib "eagle-import") (part "R-EU_R1206"))
    )
    (comp (ref "R30")
      (value "47K")
      (footprint "eagle-import:R1206")
      (libsource (lib "eagle-import") (part "R-EU_R1206"))
    )
    (comp (ref "R31")
      (value "13K")
      (footprint "eagle-import:R1206")
      (libsource (lib "eagle-import") (part "R-EU_R1206"))
    )
    (comp (ref "R32")
      (value "13K")
      (footprint "eagle-import:R1206")
      (libsource (lib "eagle-import") (part "R-EU_R1206"))
    )
    (comp (ref "C2")
      (value "100nF")
      (footprint "eagle-import:WCAP-CSGP_0805_H0.8_R")
      (libsource (lib "eagle-import") (part "WCAP-CSGP_0805_H0.8_50V(DC)_R_885012207098"))
    )
    (comp (ref "C3")
      (value "100nF")
      (footprint "eagle-import:WCAP-CSGP_0805_H0.8_R")
      (libsource (lib "eagle-import") (part "WCAP-CSGP_0805_H0.8_50V(DC)_R_885012207098"))
    )
    (comp (ref "C4")
      (value "10nF")
      (footprint "eagle-import:WCAP-CSGP_0805_H0.8_R")
      (libsource (lib "eagle-import") (part "WCAP-CSGP_0805_H0.8_50V(DC)_R_885012207092"))
    )
    (comp (ref "C5")
      (value "100nF")
      (footprint "eagle-import:WCAP-CSGP_0805_H0.8_R")
      (libsource (lib "eagle-import") (part "WCAP-CSGP_0805_H0.8_50V(DC)_R_885012207098"))
    )
    (comp (ref "C6")
      (value "100nF")
      (footprint "eagle-import:WCAP-CSGP_0805_H0.8_R")
      (libsource (lib "eagle-import") (part "WCAP-CSGP_0805_H0.8_50V(DC)_R_885012207098"))
    )
    (comp (ref "C7")
      (value "10nF")
      (footprint "eagle-import:WCAP-CSGP_0805_H0.8_R")
      (libsource (lib "eagle-import") (part "WCAP-CSGP_0805_H0.8_50V(DC)_R_885012207092"))
    )
    (comp (ref "C8")
      (value "10nF")
      (footprint "eagle-import:WCAP-CSGP_0805_H0.8_R")
      (libsource (lib "eagle-import") (part "WCAP-CSGP_0805_H0.8_50V(DC)_R_885012207092"))
    )
    (comp (ref "C9")
      (value "10nF")
      (footprint "eagle-import:WCAP-CSGP_0805_H0.8_R")
      (libsource (lib "eagle-import") (part "WCAP-CSGP_0805_H0.8_50V(DC)_R_885012207092"))
    )
    (comp (ref "D0")
      (value "33V")
      (footprint "eagle-import:WE-TVSP_DO-214AB_BIDIRECTIONAL")
      (libsource (lib "eagle-import") (part "WE-TVSP_DO-214AB_3000W_BI_824551331"))
    )
    (comp (ref "D1")
      (value "150141VS73100")
      (footprint "eagle-import:WL-SMTW_3528")
      (libsource (lib "eagle-import") (part "WL-SMTW_3528_150141VS73100"))
    )
    (comp (ref "D2")
      (value "150141VS73100")
      (footprint "eagle-import:WL-SMTW_3528")
      (libsource (lib "eagle-import") (part "WL-SMTW_3528_150141VS73100"))
    )
    (comp (ref "D3")
      (value "150141VS73100")
      (footprint "eagle-import:WL-SMTW_3528")
      (libsource (lib "eagle-import") (part "WL-SMTW_3528_150141VS73100"))
    )
    (comp (ref "D4")
      (value "150141VS73100")
      (footprint "eagle-import:WL-SMTW_3528")
      (libsource (lib "eagle-import") (part "WL-SMTW_3528_150141VS73100"))
    )
    (comp (ref "J5")
      (value "6130XX21121_61300621121")
      (footprint "eagle-import:61300621121")
      (libsource (lib "eagle-import") (part "6130XX21121_61300621121"))
    )
    (comp (ref "J9")
      (value "6130XX21121_61300621121")
      (footprint "eagle-import:61300621121")
      (libsource (lib "eagle-import") (part "6130XX21121_61300621121"))
    )
    (comp (ref "R2")
      (value "4k7")
      (footprint "eagle-import:R0805")
      (libsource (lib "eagle-import") (part "R-EU_R0805"))
    )
    (comp (ref "R4")
      (value "4k7")
      (footprint "eagle-import:R0805")
      (libsource (lib "eagle-import") (part "R-EU_R0805"))
    )
    (comp (ref "R7")
      (value "47R")
      (footprint "eagle-import:R0805")
      (libsource (lib "eagle-import") (part "R-EU_R0805"))
    )
    (comp (ref "R10")
      (value "47R")
      (footprint "eagle-import:R0805")
      (libsource (lib "eagle-import") (part "R-EU_R0805"))
    )
    (comp (ref "R13")
      (value "4k7")
      (footprint "eagle-import:R0805")
      (libsource (lib "eagle-import") (part "R-EU_R0805"))
    )
    (comp (ref "R18")
      (value "4k7")
      (footprint "eagle-import:R0805")
      (libsource (lib "eagle-import") (part "R-EU_R0805"))
    )
    (comp (ref "RX1")
      (value "470Ohm")
      (footprint "eagle-import:R1206")
      (libsource (lib "eagle-import") (part "R-EU_R1206"))
    )
    (comp (ref "RX2")
      (value "470Ohm")
      (footprint "eagle-import:R1206")
      (libsource (lib "eagle-import") (part "R-EU_R1206"))
    )
    (comp (ref "RX3")
      (value "470Ohm")
      (footprint "eagle-import:R1206")
      (libsource (lib "eagle-import") (part "R-EU_R1206"))
    )
    (comp (ref "RX4")
      (value "470Ohm")
      (footprint "eagle-import:R1206")
      (libsource (lib "eagle-import") (part "R-EU_R1206"))
    )
    (comp (ref "U2")
      (value "BTS7030-2EPA")
      (footprint "eagle-import:SOP65P600X115-15N-V")
      (libsource (lib "eagle-import") (part "BTS7030-2EPA"))
    )
    (comp (ref "U3")
      (value "BTS7030-2EPA")
      (footprint "eagle-import:SOP65P600X115-15N-V")
      (libsource (lib "eagle-import") (part "BTS7030-2EPA"))
    )
    (comp (ref "MP1")
      (value "M3 x 2.5mm")
      (footprint "eagle-import:WA-SMSI_9774025360")
      (libsource (lib "eagle-import") (part "WA-SMSI_9774XXX360_9774025360R"))
    )
    (comp (ref "MP2")
      (value "M3 x 2.5mm")
      (footprint "eagle-import:WA-SMSI_9774025360")
      (libsource (lib "eagle-import") (part "WA-SMSI_9774XXX360_9774025360R"))
    )
    (comp (ref "MP3")
      (value "M3 x 2.5mm")
      (footprint "eagle-import:WA-SMSI_9774025360")
      (libsource (lib "eagle-import") (part "WA-SMSI_9774XXX360_9774025360R"))
    )
    (comp (ref "MP4")
      (value "M3 x 2.5mm")
      (footprint "eagle-import:WA-SMSI_9774025360")
      (libsource (lib "eagle-import") (part "WA-SMSI_9774XXX360_9774025360R"))
    )
    (comp (ref "MP5")
      (value "M3 x 2.5mm")
      (footprint "eagle-import:WA-SMSI_9774025360")
      (libsource (lib "eagle-import") (part "WA-SMSI_9774XXX360_9774025360R"))
    )
    (comp (ref "MP6")
      (value "M3 x 2.5mm")
      (footprint "eagle-import:WA-SMSI_9774025360")
      (libsource (lib "eagle-import") (part "WA-SMSI_9774XXX360_9774025360R"))
    )
    (comp (ref "MP7")
      (value "M3 x 2.5mm")
      (footprint "eagle-import:WA-SMSI_9774025360")
      (libsource (lib "eagle-import") (part "WA-SMSI_9774XXX360_9774025360R"))
    )
    (comp (ref "MP8")
      (value "M3 x 2.5mm")
      (footprint "eagle-import:WA-SMSI_9774025360")
      (libsource (lib "eagle-import") (part "WA-SMSI_9774XXX360_9774025360R"))
    )
    (comp (ref "W1-J1")
      (value "61301015721")
      (footprint "eagle-import:61301015721")
      (libsource (lib "eagle-import") (part "6130XX15721_61301015721"))
    )
    (comp (ref "W1-J2")
      (value "61300615721")
      (footprint "eagle-import:61300615721")
      (libsource (lib "eagle-import") (part "6130XX15721_61300615721"))
    )
    (comp (ref "W2-J1")
      (value "61301015721")
      (footprint "eagle-import:61301015721")
      (libsource (lib "eagle-import") (part "6130XX15721_61301015721"))
    )
    (comp (ref "W2-J2")
      (value "61300615721")
      (footprint "eagle-import:61300615721")
      (libsource (lib "eagle-import") (part "6130XX15721_61300615721"))
    )
    (comp (ref "C10")
      (value "22uF")
      (footprint "eagle-import:WCAP-CSGP_1210_H2.5")
      (libsource (lib "eagle-import") (part "WCAP-CSGP_1210_H2.5_25V(DC)_885012109014"))
    )
    (comp (ref "C12")
      (value "22uF")
      (footprint "eagle-import:WCAP-CSGP_0805_H1.25_R")
      (libsource (lib "eagle-import") (part "WCAP-CSGP_0805_H1.25_10V(DC)_885012107011"))
    )
    (comp (ref "C23")
      (value "330 µF")
      (footprint "eagle-import:WCAP-ASLI_12.5X14(DXL)")
      (libsource (lib "eagle-import") (part "WCAP-ASLI_12.5X14_865080662019"))
    )
    (comp (ref "D5")
      (value "33V")
      (footprint "eagle-import:WE-TVSP_DO-214AB_BIDIRECTIONAL")
      (libsource (lib "eagle-import") (part "WE-TVSP_DO-214AB_3000W_BI_824551331"))
    )
    (comp (ref "D006")
      (value "MBRS340T3")
      (footprint "eagle-import:SMC")
      (libsource (lib "eagle-import") (part "MBRS30T34"))
    )
    (comp (ref "G1")
      (value "IFX27001TF_V50")
      (footprint "eagle-import:INF-PG-TO252-3-11_N")
      (libsource (lib "eagle-import") (part "IFX27001TF_V50"))
    )
    (comp (ref "J2")
      (value "645004114822")
      (footprint "eagle-import:645004114822")
      (libsource (lib "eagle-import") (part "645004114822"))
    )
    (comp (ref "J4")
      (value "61300421121")
      (footprint "eagle-import:61300421121")
      (libsource (lib "eagle-import") (part "6130XX21121_61300421121"))
    )
    (comp (ref "J1")
      (value "638207222005")
      (footprint "eagle-import:638207222005")
      (libsource (lib "eagle-import") (part "638207222005"))
    )
    (comp (ref "J7")
      (value "638207222005")
      (footprint "eagle-import:638207222005")
      (libsource (lib "eagle-import") (part "638207222005"))
    )
    (comp (ref "J8")
      (value "638207222007")
      (footprint "eagle-import:638207222007")
      (libsource (lib "eagle-import") (part "638207222007"))
    )
    (comp (ref "J13")
      (value "638207222005")
      (footprint "eagle-import:638207222005")
      (libsource (lib "eagle-import") (part "638207222005"))
    )
    (comp (ref "J15")
      (value "638207222008")
      (footprint "eagle-import:638207222008")
      (libsource (lib "eagle-import") (part "638207222008"))
    )
    (comp (ref "C39")
      (value "100nF")
      (footprint "eagle-import:WCAP-CSGP_1206_H0.8")
      (libsource (lib "eagle-import") (part "WCAP-CSGP_1206_H0.8_50V(DC)_885012208087"))
    )
    (comp (ref "C40")
      (value "100nF")
      (footprint "eagle-import:WCAP-CSGP_1206_H0.8")
      (libsource (lib "eagle-import") (part "WCAP-CSGP_1206_H0.8_50V(DC)_885012208087"))
    )
    (comp (ref "C41")
      (value "100nF")
      (footprint "eagle-import:WCAP-CSGP_1206_H0.8")
      (libsource (lib "eagle-import") (part "WCAP-CSGP_1206_H0.8_50V(DC)_885012208087"))
    )
    (comp (ref "C42")
      (value "100nF")
      (footprint "eagle-import:WCAP-CSGP_1206_H0.8")
      (libsource (lib "eagle-import") (part "WCAP-CSGP_1206_H0.8_50V(DC)_885012208087"))
    )
    (comp (ref "D15")
      (value "3.3Vdc")
      (footprint "eagle-import:WE-TVS_SOT143-4L")
      (libsource (lib "eagle-import") (part "WE-TVS-HS_SOT143-4L_8240136"))
    )
    (comp (ref "R39")
      (value "1K2")
      (footprint "eagle-import:R1206")
      (libsource (lib "eagle-import") (part "R-EU_R1206"))
    )
    (comp (ref "R40")
      (value "47K")
      (footprint "eagle-import:R1206")
      (libsource (lib "eagle-import") (part "R-EU_R1206"))
    )
    (comp (ref "R41")
      (value "13K")
      (footprint "eagle-import:R1206")
      (libsource (lib "eagle-import") (part "R-EU_R1206"))
    )
    (comp (ref "R42")
      (value "1K2")
      (footprint "eagle-import:R1206")
      (libsource (lib "eagle-import") (part "R-EU_R1206"))
    )
    (comp (ref "R43")
      (value "47K")
      (footprint "eagle-import:R1206")
      (libsource (lib "eagle-import") (part "R-EU_R1206"))
    )
    (comp (ref "R44")
      (value "13K")
      (footprint "eagle-import:R1206")
      (libsource (lib "eagle-import") (part "R-EU_R1206"))
    )
    (comp (ref "C1")
      (value "100nF")
      (footprint "eagle-import:WCAP-CSGP_0805_H0.8_R")
      (libsource (lib "eagle-import") (part "WCAP-CSGP_0805_H0.8_50V(DC)_R_885012207098"))
    )
    (comp (ref "C13")
      (value "100nF")
      (footprint "eagle-import:WCAP-CSGP_0805_H0.8_R")
      (libsource (lib "eagle-import") (part "WCAP-CSGP_0805_H0.8_50V(DC)_R_885012207098"))
    )
    (comp (ref "C14")
      (value "10nF")
      (footprint "eagle-import:WCAP-CSGP_0805_H0.8_R")
      (libsource (lib "eagle-import") (part "WCAP-CSGP_0805_H0.8_50V(DC)_R_885012207092"))
    )
    (comp (ref "C16")
      (value "10nF")
      (footprint "eagle-import:WCAP-CSGP_0805_H0.8_R")
      (libsource (lib "eagle-import") (part "WCAP-CSGP_0805_H0.8_50V(DC)_R_885012207092"))
    )
    (comp (ref "C18")
      (value "100nF")
      (footprint "eagle-import:WCAP-CSGP_0805_H0.8_R")
      (libsource (lib "eagle-import") (part "WCAP-CSGP_0805_H0.8_50V(DC)_R_885012207098"))
    )
    (comp (ref "C20")
      (value "100nF")
      (footprint "eagle-import:WCAP-CSGP_0805_H0.8_R")
      (libsource (lib "eagle-import") (part "WCAP-CSGP_0805_H0.8_50V(DC)_R_885012207098"))
    )
    (comp (ref "C21")
      (value "10nF")
      (footprint "eagle-import:WCAP-CSGP_0805_H0.8_R")
      (libsource (lib "eagle-import") (part "WCAP-CSGP_0805_H0.8_50V(DC)_R_885012207092"))
    )
    (comp (ref "C22")
      (value "10nF")
      (footprint "eagle-import:WCAP-CSGP_0805_H0.8_R")
      (libsource (lib "eagle-import") (part "WCAP-CSGP_0805_H0.8_50V(DC)_R_885012207092"))
    )
    (comp (ref "D7")
      (value "150141VS73100")
      (footprint "eagle-import:WL-SMTW_3528")
      (libsource (lib "eagle-import") (part "WL-SMTW_3528_150141VS73100"))
    )
    (comp (ref "D8")
      (value "150141VS73100")
      (footprint "eagle-import:WL-SMTW_3528")
      (libsource (lib "eagle-import") (part "WL-SMTW_3528_150141VS73100"))
    )
    (comp (ref "D9")
      (value "150141VS73100")
      (footprint "eagle-import:WL-SMTW_3528")
      (libsource (lib "eagle-import") (part "WL-SMTW_3528_150141VS73100"))
    )
    (comp (ref "D10")
      (value "150141VS73100")
      (footprint "eagle-import:WL-SMTW_3528")
      (libsource (lib "eagle-import") (part "WL-SMTW_3528_150141VS73100"))
    )
    (comp (ref "R5")
      (value "4k7")
      (footprint "eagle-import:R0805")
      (libsource (lib "eagle-import") (part "R-EU_R0805"))
    )
    (comp (ref "R6")
      (value "4k7")
      (footprint "eagle-import:R0805")
      (libsource (lib "eagle-import") (part "R-EU_R0805"))
    )
    (comp (ref "R8")
      (value "47R")
      (footprint "eagle-import:R0805")
      (libsource (lib "eagle-import") (part "R-EU_R0805"))
    )
    (comp (ref "R9")
      (value "4k7")
      (footprint "eagle-import:R0805")
      (libsource (lib "eagle-import") (part "R-EU_R0805"))
    )
    (comp (ref "R11")
      (value "4k7")
      (footprint "eagle-import:R0805")
      (libsource (lib "eagle-import") (part "R-EU_R0805"))
    )
    (comp (ref "R12")
      (value "47R")
      (footprint "eagle-import:R0805")
      (libsource (lib "eagle-import") (part "R-EU_R0805"))
    )
    (comp (ref "RX5")
      (value "470Ohm")
      (footprint "eagle-import:R1206")
      (libsource (lib "eagle-import") (part "R-EU_R1206"))
    )
    (comp (ref "RX6")
      (value "470Ohm")
      (footprint "eagle-import:R1206")
      (libsource (lib "eagle-import") (part "R-EU_R1206"))
    )
    (comp (ref "RX7")
      (value "470Ohm")
      (footprint "eagle-import:R1206")
      (libsource (lib "eagle-import") (part "R-EU_R1206"))
    )
    (comp (ref "RX8")
      (value "470Ohm")
      (footprint "eagle-import:R1206")
      (libsource (lib "eagle-import") (part "R-EU_R1206"))
    )
    (comp (ref "U5")
      (value "BTS7030-2EPA")
      (footprint "eagle-import:SOP65P600X115-15N-V")
      (libsource (lib "eagle-import") (part "BTS7030-2EPA"))
    )
    (comp (ref "U6")
      (value "BTS7030-2EPA")
      (footprint "eagle-import:SOP65P600X115-15N-V")
      (libsource (lib "eagle-import") (part "BTS7030-2EPA"))
    )
    (comp (ref "C31")
      (value "100nF")
      (footprint "eagle-import:WCAP-CSGP_1206_H0.8")
      (libsource (lib "eagle-import") (part "WCAP-CSGP_1206_H0.8_50V(DC)_885012208087"))
    )
    (comp (ref "C32")
      (value "100nF")
      (footprint "eagle-import:WCAP-CSGP_1206_H0.8")
      (libsource (lib "eagle-import") (part "WCAP-CSGP_1206_H0.8_50V(DC)_885012208087"))
    )
    (comp (ref "C33")
      (value "100nF")
      (footprint "eagle-import:WCAP-CSGP_1206_H0.8")
      (libsource (lib "eagle-import") (part "WCAP-CSGP_1206_H0.8_50V(DC)_885012208087"))
    )
    (comp (ref "C34")
      (value "100nF")
      (footprint "eagle-import:WCAP-CSGP_1206_H0.8")
      (libsource (lib "eagle-import") (part "WCAP-CSGP_1206_H0.8_50V(DC)_885012208087"))
    )
    (comp (ref "D13")
      (value "3.3Vdc")
      (footprint "eagle-import:WE-TVS_SOT143-4L")
      (libsource (lib "eagle-import") (part "WE-TVS-HS_SOT143-4L_8240136"))
    )
    (comp (ref "R21")
      (value "1K2")
      (footprint "eagle-import:R1206")
      (libsource (lib "eagle-import") (part "R-EU_R1206"))
    )
    (comp (ref "R22")
      (value "47K")
      (footprint "eagle-import:R1206")
      (libsource (lib "eagle-import") (part "R-EU_R1206"))
    )
    (comp (ref "R23")
      (value "13K")
      (footprint "eagle-import:R1206")
      (libsource (lib "eagle-import") (part "R-EU_R1206"))
    )
    (comp (ref "R24")
      (value "1K2")
      (footprint "eagle-import:R1206")
      (libsource (lib "eagle-import") (part "R-EU_R1206"))
    )
    (comp (ref "R25")
      (value "47K")
      (footprint "eagle-import:R1206")
      (libsource (lib "eagle-import") (part "R-EU_R1206"))
    )
    (comp (ref "R26")
      (value "13K")
      (footprint "eagle-import:R1206")
      (libsource (lib "eagle-import") (part "R-EU_R1206"))
    )
    (comp (ref "ESP32-J1")
      (value "61302211821")
      (footprint "eagle-import:61302211821")
      (libsource (lib "eagle-import") (part "6130XX11821_61302211821"))
    )
    (comp (ref "ESP32-J3")
      (value "61302211821")
      (footprint "eagle-import:61302211821")
      (libsource (lib "eagle-import") (part "6130XX11821_61302211821"))
    )
    (comp (ref "R14")
      (value "13K")
      (footprint "eagle-import:R1206")
      (libsource (lib "eagle-import") (part "R-EU_R1206"))
    )
    (comp (ref "R15")
      (value "13K")
      (footprint "eagle-import:R1206")
      (libsource (lib "eagle-import") (part "R-EU_R1206"))
    )
  )
  (nets
    (net (code "1") (name "+3V3") (class "Default")
      (node (ref "C19") (pin "1") (pinfunction "1_1") (pintype "passive"))
      (node (ref "D12") (pin "4") (pinfunction "VDD_4") (pintype "passive"))
      (node (ref "D13") (pin "4") (pinfunction "VDD_4") (pintype "passive"))
      (node (ref "D15") (pin "4") (pinfunction "VDD_4") (pintype "passive"))
      (node (ref "D17") (pin "4") (pinfunction "VDD_4") (pintype "passive"))
      (node (ref "ESP32-J1") (pin "1") (pinfunction "1_1") (pintype "passive"))
      (node (ref "ESP32-J1") (pin "2") (pinfunction "2_2") (pintype "passive"))
      (node (ref "U4") (pin "5") (pinfunction "VIO_5") (pintype "input"))
      (node (ref "W1-J1") (pin "7") (pinfunction "7_7") (pintype "passive"))
      (node (ref "W1-J1") (pin "8") (pinfunction "8_8") (pintype "passive"))
      (node (ref "W1-J2") (pin "1") (pinfunction "1_1") (pintype "passive"))
      (node (ref "W2-J1") (pin "7") (pinfunction "7_7") (pintype "passive"))
      (node (ref "W2-J1") (pin "8") (pinfunction "8_8") (pintype "passive"))
      (node (ref "W2-J2") (pin "1") (pinfunction "1_1") (pintype "passive"))
    )
    (net (code "2") (name "+5V") (class "Default")
      (node (ref "C12") (pin "2") (pinfunction "2_2") (pintype "passive"))
      (node (ref "C17") (pin "1") (pinfunction "1_1") (pintype "passive"))
      (node (ref "ESP32-J1") (pin "21") (pinfunction "21_21") (pintype "passive"))
      (node (ref "G1") (pin "2") (pinfunction "Q_2") (pintype "power_in"))
      (node (ref "J4") (pin "1") (pinfunction "1_1") (pintype "passive"))
      (node (ref "J4") (pin "2") (pinfunction "2_2") (pintype "passive"))
      (node (ref "J4") (pin "3") (pinfunction "3_3") (pintype "passive"))
      (node (ref "J4") (pin "4") (pinfunction "4_4") (pintype "passive"))
      (node (ref "U4") (pin "3") (pinfunction "VCC_3") (pintype "input"))
    )
    (net (code "3") (name "AGNDU2") (class "Default")
      (node (ref "C6") (pin "2") (pinfunction "2_2") (pintype "passive"))
      (node (ref "R10") (pin "2") (pinfunction "2_2") (pintype "passive"))
      (node (ref "U2") (pin "1") (pinfunction "GND_1") (pintype "power_in"))
    )
    (net (code "4") (name "AGNDU3") (class "Default")
      (node (ref "C3") (pin "2") (pinfunction "2_2") (pintype "passive"))
      (node (ref "R7") (pin "2") (pinfunction "2_2") (pintype "passive"))
      (node (ref "U3") (pin "1") (pinfunction "GND_1") (pintype "power_in"))
    )
    (net (code "5") (name "AGNDU4") (class "Default")
      (node (ref "C13") (pin "2") (pinfunction "2_2") (pintype "passive"))
      (node (ref "R8") (pin "2") (pinfunction "2_2") (pintype "passive"))
      (node (ref "U5") (pin "1") (pinfunction "GND_1") (pintype "power_in"))
    )
    (net (code "6") (name "AGNDU5") (class "Default")
      (node (ref "C20") (pin "2") (pinfunction "2_2") (pintype "passive"))
      (node (ref "R12") (pin "2") (pinfunction "2_2") (pintype "passive"))
      (node (ref "U6") (pin "1") (pinfunction "GND_1") (pintype "power_in"))
    )
    (net (code "7") (name "BOOT") (class "Default")
      (node (ref "ESP32-J3") (pin "14") (pinfunction "14_14") (pintype "passive"))
    )
    (net (code "8") (name "CAN1_RXD") (class "Default")
      (node (ref "ESP32-J1") (pin "5") (pinfunction "5_5") (pintype "passive"))
      (node (ref "U4") (pin "4") (pinfunction "RXD_4") (pintype "output"))
    )
    (net (code "9") (name "CAN1_TXD") (class "Default")
      (node (ref "ESP32-J1") (pin "4") (pinfunction "4_4") (pintype "passive"))
      (node (ref "U4") (pin "1") (pinfunction "TXD_1") (pintype "input"))
    )
    (net (code "10") (name "CAN_N") (class "Default")
      (node (ref "D11") (pin "1") (pinfunction "I/O1_1") (pintype "passive"))
      (node (ref "J2") (pin "1") (pinfunction "1_1") (pintype "passive"))
      (node (ref "R3") (pin "2") (pinfunction "2_2") (pintype "passive"))
      (node (ref "U4") (pin "6") (pinfunction "CANL_6") (pintype "bidirectional"))
    )
    (net (code "11") (name "CAN_P") (class "Default")
      (node (ref "D11") (pin "2") (pinfunction "I/O2_2") (pintype "passive"))
      (node (ref "J2") (pin "2") (pinfunction "2_2") (pintype "passive"))
      (node (ref "R1") (pin "2") (pinfunction "2_2") (pintype "passive"))
      (node (ref "U4") (pin "7") (pinfunction "CANH_7") (pintype "bidirectional"))
    )
    (net (code "12") (name "CI1") (class "Default")
      (node (ref "C32") (pin "1") (pinfunction "1_1") (pintype "passive"))
      (node (ref "D13") (pin "3") (pinfunction "2_3") (pintype "passive"))
      (node (ref "ESP32-J1") (pin "19") (pinfunction "19_19") (pintype "passive"))
      (node (ref "R22") (pin "1") (pinfunction "1_1") (pintype "passive"))
      (node (ref "R23") (pin "2") (pinfunction "2_2") (pintype "passive"))
    )
    (net (code "13") (name "CI2") (class "Default")
      (node (ref "C34") (pin "1") (pinfunction "1_1") (pintype "passive"))
      (node (ref "D13") (pin "2") (pinfunction "1_2") (pintype "passive"))
      (node (ref "ESP32-J1") (pin "18") (pinfunction "18_18") (pintype "passive"))
      (node (ref "R25") (pin "1") (pinfunction "1_1") (pintype "passive"))
      (node (ref "R26") (pin "2") (pinfunction "2_2") (pintype "passive"))
    )
    (net (code "14") (name "CI3") (class "Default")
      (node (ref "C40") (pin "1") (pinfunction "1_1") (pintype "passive"))
      (node (ref "D15") (pin "3") (pinfunction "2_3") (pintype "passive"))
      (node (ref "ESP32-J1") (pin "15") (pinfunction "15_15") (pintype "passive"))
      (node (ref "R40") (pin "1") (pinfunction "1_1") (pintype "passive"))
      (node (ref "R41") (pin "2") (pinfunction "2_2") (pintype "passive"))
    )
    (net (code "15") (name "CI4") (class "Default")
      (node (ref "C42") (pin "1") (pinfunction "1_1") (pintype "passive"))
      (node (ref "D15") (pin "2") (pinfunction "1_2") (pintype "passive"))
      (node (ref "ESP32-J1") (pin "13") (pinfunction "13_13") (pintype "passive"))
      (node (ref "R43") (pin "1") (pinfunction "1_1") (pintype "passive"))
      (node (ref "R44") (pin "2") (pinfunction "2_2") (pintype "passive"))
    )
    (net (code "16") (name "CI5") (class "Default")
      (node (ref "C48") (pin "1") (pinfunction "1_1") (pintype "passive"))
      (node (ref "D17") (pin "3") (pinfunction "2_3") (pintype "passive"))
      (node (ref "ESP32-J1") (pin "11") (pinfunction "11_11") (pintype "passive"))
      (node (ref "R52") (pin "1") (pinfunction "1_1") (pintype "passive"))
      (node (ref "R53") (pin "2") (pinfunction "2_2") (pintype "passive"))
    )
    (net (code "17") (name "CI6") (class "Default")
      (node (ref "C50") (pin "1") (pinfunction "1_1") (pintype "passive"))
      (node (ref "D17") (pin "2") (pinfunction "1_2") (pintype "passive"))
      (node (ref "ESP32-J1") (pin "10") (pinfunction "10_10") (pintype "passive"))
      (node (ref "R55") (pin "1") (pinfunction "1_1") (pintype "passive"))
      (node (ref "R56") (pin "2") (pinfunction "2_2") (pintype "passive"))
    )
    (net (code "18") (name "CI7") (class "Default")
      (node (ref "C27") (pin "1") (pinfunction "1_1") (pintype "passive"))
      (node (ref "D12") (pin "3") (pinfunction "2_3") (pintype "passive"))
      (node (ref "ESP32-J1") (pin "7") (pinfunction "7_7") (pintype "passive"))
      (node (ref "R30") (pin "1") (pinfunction "1_1") (pintype "passive"))
      (node (ref "R32") (pin "2") (pinfunction "2_2") (pintype "passive"))
    )
    (net (code "19") (name "CI8") (class "Default")
      (node (ref "C26") (pin "1") (pinfunction "1_1") (pintype "passive"))
      (node (ref "D12") (pin "2") (pinfunction "1_2") (pintype "passive"))
      (node (ref "ESP32-J1") (pin "6") (pinfunction "6_6") (pintype "passive"))
      (node (ref "R29") (pin "1") (pinfunction "1_1") (pintype "passive"))
      (node (ref "R31") (pin "2") (pinfunction "2_2") (pintype "passive"))
    )
    (net (code "20") (name "CS0") (class "Default")
      (node (ref "ESP32-J1") (pin "14") (pinfunction "14_14") (pintype "passive"))
      (node (ref "W1-J1") (pin "6") (pinfunction "6_6") (pintype "passive"))
    )
    (net (code "21") (name "CS1") (class "Default")
      (node (ref "ESP32-J1") (pin "12") (pinfunction "12_12") (pintype "passive"))
      (node (ref "W2-J1") (pin "6") (pinfunction "6_6") (pintype "passive"))
    )
    (net (code "22") (name "ECU_GND") (class "Default")
      (node (ref "C1") (pin "2") (pinfunction "2_2") (pintype "passive"))
      (node (ref "C10") (pin "1") (pinfunction "1_1") (pintype "passive"))
      (node (ref "C12") (pin "1") (pinfunction "1_1") (pintype "passive"))
      (node (ref "C15") (pin "2") (pinfunction "2_2") (pintype "passive"))
      (node (ref "C17") (pin "2") (pinfunction "2_2") (pintype "passive"))
      (node (ref "C18") (pin "2") (pinfunction "2_2") (pintype "passive"))
      (node (ref "C19") (pin "2") (pinfunction "2_2") (pintype "passive"))
      (node (ref "C2") (pin "2") (pinfunction "2_2") (pintype "passive"))
      (node (ref "C23") (pin "2") (pinfunction "-_2") (pintype "passive"))
      (node (ref "C24") (pin "2") (pinfunction "2_2") (pintype "passive"))
      (node (ref "C25") (pin "2") (pinfunction "2_2") (pintype "passive"))
      (node (ref "C26") (pin "2") (pinfunction "2_2") (pintype "passive"))
      (node (ref "C27") (pin "2") (pinfunction "2_2") (pintype "passive"))
      (node (ref "C31") (pin "2") (pinfunction "2_2") (pintype "passive"))
      (node (ref "C32") (pin "2") (pinfunction "2_2") (pintype "passive"))
      (node (ref "C33") (pin "2") (pinfunction "2_2") (pintype "passive"))
      (node (ref "C34") (pin "2") (pinfunction "2_2") (pintype "passive"))
      (node (ref "C39") (pin "2") (pinfunction "2_2") (pintype "passive"))
      (node (ref "C40") (pin "2") (pinfunction "2_2") (pintype "passive"))
      (node (ref "C41") (pin "2") (pinfunction "2_2") (pintype "passive"))
      (node (ref "C42") (pin "2") (pinfunction "2_2") (pintype "passive"))
      (node (ref "C47") (pin "2") (pinfunction "2_2") (pintype "passive"))
      (node (ref "C48") (pin "2") (pinfunction "2_2") (pintype "passive"))
      (node (ref "C49") (pin "2") (pinfunction "2_2") (pintype "passive"))
      (node (ref "C5") (pin "2") (pinfunction "2_2") (pintype "passive"))
      (node (ref "C50") (pin "2") (pinfunction "2_2") (pintype "passive"))
      (node (ref "D11") (pin "3") (pinfunction "GND_3") (pintype "passive"))
      (node (ref "D12") (pin "1") (pinfunction "GND_1") (pintype "passive"))
      (node (ref "D13") (pin "1") (pinfunction "GND_1") (pintype "passive"))
      (node (ref "D15") (pin "1") (pinfunction "GND_1") (pintype "passive"))
      (node (ref "D17") (pin "1") (pinfunction "GND_1") (pintype "passive"))
      (node (ref "D5") (pin "1") (pinfunction "1_1") (pintype "passive"))
      (node (ref "ESP32-J1") (pin "22") (pinfunction "22_22") (pintype "passive"))
      (node (ref "ESP32-J3") (pin "1") (pinfunction "1_1") (pintype "passive"))
      (node (ref "ESP32-J3") (pin "21") (pinfunction "21_21") (pintype "passive"))
      (node (ref "ESP32-J3") (pin "22") (pinfunction "22_22") (pintype "passive"))
      (node (ref "G1") (pin "1") (pinfunction "GND/ADJ_1") (pintype "power_in"))
      (node (ref "J2") (pin "4") (pinfunction "4_4") (pintype "passive"))
      (node (ref "J7") (pin "1") (pinfunction "1_1") (pintype "passive"))
      (node (ref "J7") (pin "2") (pinfunction "2_2") (pintype "passive"))
      (node (ref "J7") (pin "A1") (pinfunction "1_A1") (pintype "passive"))
      (node (ref "J7") (pin "A2") (pinfunction "2_A2") (pintype "passive"))
      (node (ref "J9") (pin "2") (pinfunction "2_2") (pintype "passive"))
      (node (ref "J9") (pin "4") (pinfunction "4_4") (pintype "passive"))
      (node (ref "J9") (pin "6") (pinfunction "6_6") (pintype "passive"))
      (node (ref "MP5") (pin "1") (pinfunction "1_1") (pintype "passive"))
      (node (ref "MP6") (pin "1") (pinfunction "1_1") (pintype "passive"))
      (node (ref "MP7") (pin "1") (pinfunction "1_1") (pintype "passive"))
      (node (ref "MP8") (pin "1") (pinfunction "1_1") (pintype "passive"))
      (node (ref "R10") (pin "1") (pinfunction "1_1") (pintype "passive"))
      (node (ref "R12") (pin "1") (pinfunction "1_1") (pintype "passive"))
      (node (ref "R14") (pin "1") (pinfunction "1_1") (pintype "passive"))
      (node (ref "R15") (pin "1") (pinfunction "1_1") (pintype "passive"))
      (node (ref "R21") (pin "1") (pinfunction "1_1") (pintype "passive"))
      (node (ref "R23") (pin "1") (pinfunction "1_1") (pintype "passive"))
      (node (ref "R24") (pin "1") (pinfunction "1_1") (pintype "passive"))
      (node (ref "R26") (pin "1") (pinfunction "1_1") (pintype "passive"))
      (node (ref "R27") (pin "1") (pinfunction "1_1") (pintype "passive"))
      (node (ref "R28") (pin "1") (pinfunction "1_1") (pintype "passive"))
      (node (ref "R31") (pin "1") (pinfunction "1_1") (pintype "passive"))
      (node (ref "R32") (pin "1") (pinfunction "1_1") (pintype "passive"))
      (node (ref "R39") (pin "1") (pinfunction "1_1") (pintype "passive"))
      (node (ref "R41") (pin "1") (pinfunction "1_1") (pintype "passive"))
      (node (ref "R42") (pin "1") (pinfunction "1_1") (pintype "passive"))
      (node (ref "R44") (pin "1") (pinfunction "1_1") (pintype "passive"))
      (node (ref "R51") (pin "1") (pinfunction "1_1") (pintype "passive"))
      (node (ref "R53") (pin "1") (pinfunction "1_1") (pintype "passive"))
      (node (ref "R54") (pin "1") (pinfunction "1_1") (pintype "passive"))
      (node (ref "R56") (pin "1") (pinfunction "1_1") (pintype "passive"))
      (node (ref "R7") (pin "1") (pinfunction "1_1") (pintype "passive"))
      (node (ref "R8") (pin "1") (pinfunction "1_1") (pintype "passive"))
      (node (ref "U4") (pin "2") (pinfunction "GND_2") (pintype "power_in"))
      (node (ref "U4") (pin "8") (pinfunction "NEN_8") (pintype "input"))
      (node (ref "W1-J1") (pin "1") (pinfunction "1_1") (pintype "passive"))
      (node (ref "W1-J1") (pin "2") (pinfunction "2_2") (pintype "passive"))
      (node (ref "W1-J2") (pin "6") (pinfunction "6_6") (pintype "passive"))
      (node (ref "W2-J1") (pin "1") (pinfunction "1_1") (pintype "passive"))
      (node (ref "W2-J1") (pin "2") (pinfunction "2_2") (pintype "passive"))
      (node (ref "W2-J2") (pin "6") (pinfunction "6_6") (pintype "passive"))
    )
    (net (code "23") (name "ECU_PWR") (class "Default")
      (node (ref "D006") (pin "A") (pinfunction "A_A") (pintype "passive"))
      (node (ref "D5") (pin "2") (pinfunction "2_2") (pintype "passive"))
      (node (ref "J2") (pin "3") (pinfunction "3_3") (pintype "passive"))
      (node (ref "J5") (pin "2") (pinfunction "2_2") (pintype "passive"))
      (node (ref "J5") (pin "4") (pinfunction "4_4") (pintype "passive"))
      (node (ref "J5") (pin "6") (pinfunction "6_6") (pintype "passive"))
      (node (ref "J7") (pin "3") (pinfunction "3_3") (pintype "passive"))
      (node (ref "J7") (pin "4") (pinfunction "4_4") (pintype "passive"))
      (node (ref "J7") (pin "A3") (pinfunction "3_A3") (pintype "passive"))
      (node (ref "J7") (pin "A4") (pinfunction "4_A4") (pintype "passive"))
    )
    (net (code "24") (name "I1") (class "Default")
      (node (ref "C31") (pin "1") (pinfunction "1_1") (pintype "passive"))
      (node (ref "J7") (pin "5") (pinfunction "5_5") (pintype "passive"))
      (node (ref "J7") (pin "A5") (pinfunction "5_A5") (pintype "passive"))
      (node (ref "R21") (pin "2") (pinfunction "2_2") (pintype "passive"))
      (node (ref "R22") (pin "2") (pinfunction "2_2") (pintype "passive"))
    )
    (net (code "25") (name "I2") (class "Default")
      (node (ref "C33") (pin "1") (pinfunction "1_1") (pintype "passive"))
      (node (ref "J8") (pin "1") (pinfunction "1_1") (pintype "passive"))
      (node (ref "J8") (pin "A1") (pinfunction "1_A1") (pintype "passive"))
      (node (ref "R24") (pin "2") (pinfunction "2_2") (pintype "passive"))
      (node (ref "R25") (pin "2") (pinfunction "2_2") (pintype "passive"))
    )
    (net (code "26") (name "I3") (class "Default")
      (node (ref "C39") (pin "1") (pinfunction "1_1") (pintype "passive"))
      (node (ref "J8") (pin "2") (pinfunction "2_2") (pintype "passive"))
      (node (ref "J8") (pin "A2") (pinfunction "2_A2") (pintype "passive"))
      (node (ref "R39") (pin "2") (pinfunction "2_2") (pintype "passive"))
      (node (ref "R40") (pin "2") (pinfunction "2_2") (pintype "passive"))
    )
    (net (code "27") (name "I4") (class "Default")
      (node (ref "C41") (pin "1") (pinfunction "1_1") (pintype "passive"))
      (node (ref "J8") (pin "3") (pinfunction "3_3") (pintype "passive"))
      (node (ref "J8") (pin "A3") (pinfunction "3_A3") (pintype "passive"))
      (node (ref "R42") (pin "2") (pinfunction "2_2") (pintype "passive"))
      (node (ref "R43") (pin "2") (pinfunction "2_2") (pintype "passive"))
    )
    (net (code "28") (name "I5") (class "Default")
      (node (ref "C47") (pin "1") (pinfunction "1_1") (pintype "passive"))
      (node (ref "J8") (pin "4") (pinfunction "4_4") (pintype "passive"))
      (node (ref "J8") (pin "A4") (pinfunction "4_A4") (pintype "passive"))
      (node (ref "R51") (pin "2") (pinfunction "2_2") (pintype "passive"))
      (node (ref "R52") (pin "2") (pinfunction "2_2") (pintype "passive"))
    )
    (net (code "29") (name "I6") (class "Default")
      (node (ref "C49") (pin "1") (pinfunction "1_1") (pintype "passive"))
      (node (ref "J8") (pin "5") (pinfunction "5_5") (pintype "passive"))
      (node (ref "J8") (pin "A5") (pinfunction "5_A5") (pintype "passive"))
      (node (ref "R54") (pin "2") (pinfunction "2_2") (pintype "passive"))
      (node (ref "R55") (pin "2") (pinfunction "2_2") (pintype "passive"))
    )
    (net (code "30") (name "I7") (class "Default")
      (node (ref "C25") (pin "1") (pinfunction "1_1") (pintype "passive"))
      (node (ref "J8") (pin "6") (pinfunction "6_6") (pintype "passive"))
      (node (ref "J8") (pin "A6") (pinfunction "6_A6") (pintype "passive"))
      (node (ref "R28") (pin "2") (pinfunction "2_2") (pintype "passive"))
      (node (ref "R30") (pin "2") (pinfunction "2_2") (pintype "passive"))
    )
    (net (code "31") (name "I8") (class "Default")
      (node (ref "C24") (pin "1") (pinfunction "1_1") (pintype "passive"))
      (node (ref "J8") (pin "7") (pinfunction "7_7") (pintype "passive"))
      (node (ref "J8") (pin "A7") (pinfunction "7_A7") (pintype "passive"))
      (node (ref "R27") (pin "2") (pinfunction "2_2") (pintype "passive"))
      (node (ref "R29") (pin "2") (pinfunction "2_2") (pintype "passive"))
    )
    (net (code "32") (name "INT0") (class "Default")
      (node (ref "ESP32-J3") (pin "16") (pinfunction "16_16") (pintype "passive"))
      (node (ref "W1-J2") (pin "5") (pinfunction "5_5") (pintype "passive"))
    )
    (net (code "33") (name "INT1") (class "Default")
      (node (ref "ESP32-J3") (pin "15") (pinfunction "15_15") (pintype "passive"))
      (node (ref "W2-J2") (pin "5") (pinfunction "5_5") (pintype "passive"))
    )
    (net (code "34") (name "MISO") (class "Default")
      (node (ref "ESP32-J1") (pin "20") (pinfunction "20_20") (pintype "passive"))
      (node (ref "W1-J1") (pin "4") (pinfunction "4_4") (pintype "passive"))
      (node (ref "W2-J1") (pin "4") (pinfunction "4_4") (pintype "passive"))
    )
    (net (code "35") (name "MOSI") (class "Default")
      (node (ref "ESP32-J1") (pin "17") (pinfunction "17_17") (pintype "passive"))
      (node (ref "W1-J1") (pin "3") (pinfunction "3_3") (pintype "passive"))
      (node (ref "W2-J1") (pin "3") (pinfunction "3_3") (pintype "passive"))
    )
    (net (code "36") (name "Net-(C15-Pad1)") (class "Default")
      (node (ref "C15") (pin "1") (pinfunction "1_1") (pintype "passive"))
      (node (ref "R1") (pin "1") (pinfunction "1_1") (pintype "passive"))
      (node (ref "R3") (pin "1") (pinfunction "1_1") (pintype "passive"))
    )
    (net (code "37") (name "Net-(C23-+)") (class "Default")
      (node (ref "C10") (pin "2") (pinfunction "2_2") (pintype "passive"))
      (node (ref "C23") (pin "1") (pinfunction "+_1") (pintype "passive"))
      (node (ref "D006") (pin "C") (pinfunction "C_C") (pintype "passive"))
      (node (ref "G1") (pin "3") (pinfunction "I_3") (pintype "power_in"))
    )
    (net (code "38") (name "Net-(D1--)") (class "Default")
      (node (ref "D1") (pin "1") (pinfunction "-_1") (pintype "passive"))
      (node (ref "RX1") (pin "2") (pinfunction "2_2") (pintype "passive"))
    )
    (net (code "39") (name "Net-(D2--)") (class "Default")
      (node (ref "D2") (pin "1") (pinfunction "-_1") (pintype "passive"))
      (node (ref "RX2") (pin "1") (pinfunction "1_1") (pintype "passive"))
    )
    (net (code "40") (name "Net-(D3--)") (class "Default")
      (node (ref "D3") (pin "1") (pinfunction "-_1") (pintype "passive"))
      (node (ref "RX3") (pin "2") (pinfunction "2_2") (pintype "passive"))
    )
    (net (code "41") (name "Net-(D4--)") (class "Default")
      (node (ref "D4") (pin "1") (pinfunction "-_1") (pintype "passive"))
      (node (ref "RX4") (pin "1") (pinfunction "1_1") (pintype "passive"))
    )
    (net (code "42") (name "Net-(D7--)") (class "Default")
      (node (ref "D7") (pin "1") (pinfunction "-_1") (pintype "passive"))
      (node (ref "RX6") (pin "1") (pinfunction "1_1") (pintype "passive"))
    )
    (net (code "43") (name "Net-(D8--)") (class "Default")
      (node (ref "D8") (pin "1") (pinfunction "-_1") (pintype "passive"))
      (node (ref "RX7") (pin "2") (pinfunction "2_2") (pintype "passive"))
    )
    (net (code "44") (name "Net-(D9--)") (class "Default")
      (node (ref "D9") (pin "1") (pinfunction "-_1") (pintype "passive"))
      (node (ref "RX5") (pin "1") (pinfunction "1_1") (pintype "passive"))
    )
    (net (code "45") (name "Net-(D10--)") (class "Default")
      (node (ref "D10") (pin "1") (pinfunction "-_1") (pintype "passive"))
      (node (ref "RX8") (pin "2") (pinfunction "2_2") (pintype "passive"))
    )
    (net (code "46") (name "Net-(U2-IN0)") (class "Default")
      (node (ref "R18") (pin "2") (pinfunction "2_2") (pintype "passive"))
      (node (ref "U2") (pin "2") (pinfunction "IN0_2") (pintype "input"))
    )
    (net (code "47") (name "Net-(U2-IN1)") (class "Default")
      (node (ref "R13") (pin "2") (pinfunction "2_2") (pintype "passive"))
      (node (ref "U2") (pin "6") (pinfunction "IN1_6") (pintype "input"))
    )
    (net (code "48") (name "Net-(U3-IN0)") (class "Default")
      (node (ref "R2") (pin "2") (pinfunction "2_2") (pintype "passive"))
      (node (ref "U3") (pin "2") (pinfunction "IN0_2") (pintype "input"))
    )
    (net (code "49") (name "Net-(U3-IN1)") (class "Default")
      (node (ref "R4") (pin "2") (pinfunction "2_2") (pintype "passive"))
      (node (ref "U3") (pin "6") (pinfunction "IN1_6") (pintype "input"))
    )
    (net (code "50") (name "Net-(U5-IN0)") (class "Default")
      (node (ref "R5") (pin "2") (pinfunction "2_2") (pintype "passive"))
      (node (ref "U5") (pin "2") (pinfunction "IN0_2") (pintype "input"))
    )
    (net (code "51") (name "Net-(U5-IN1)") (class "Default")
      (node (ref "R6") (pin "2") (pinfunction "2_2") (pintype "passive"))
      (node (ref "U5") (pin "6") (pinfunction "IN1_6") (pintype "input"))
    )
    (net (code "52") (name "Net-(U6-IN0)") (class "Default")
      (node (ref "R9") (pin "2") (pinfunction "2_2") (pintype "passive"))
      (node (ref "U6") (pin "2") (pinfunction "IN0_2") (pintype "input"))
    )
    (net (code "53") (name "Net-(U6-IN1)") (class "Default")
      (node (ref "R11") (pin "2") (pinfunction "2_2") (pintype "passive"))
      (node (ref "U6") (pin "6") (pinfunction "IN1_6") (pintype "input"))
    )
    (net (code "54") (name "PWR") (class "Default")
      (node (ref "C1") (pin "1") (pinfunction "1_1") (pintype "passive"))
      (node (ref "C13") (pin "1") (pinfunction "1_1") (pintype "passive"))
      (node (ref "C18") (pin "1") (pinfunction "1_1") (pintype "passive"))
      (node (ref "C2") (pin "1") (pinfunction "1_1") (pintype "passive"))
      (node (ref "C20") (pin "1") (pinfunction "1_1") (pintype "passive"))
      (node (ref "C3") (pin "1") (pinfunction "1_1") (pintype "passive"))
      (node (ref "C5") (pin "1") (pinfunction "1_1") (pintype "passive"))
      (node (ref "C6") (pin "1") (pinfunction "1_1") (pintype "passive"))
      (node (ref "D0") (pin "2") (pinfunction "2_2") (pintype "passive"))
      (node (ref "J13") (pin "4") (pinfunction "4_4") (pintype "passive"))
      (node (ref "J13") (pin "A4") (pinfunction "4_A4") (pintype "passive"))
      (node (ref "J5") (pin "1") (pinfunction "1_1") (pintype "passive"))
      (node (ref "J5") (pin "3") (pinfunction "3_3") (pintype "passive"))
      (node (ref "J5") (pin "5") (pinfunction "5_5") (pintype "passive"))
      (node (ref "U2") (pin "15") (pinfunction "VS_15") (pintype "power_in"))
      (node (ref "U3") (pin "15") (pinfunction "VS_15") (pintype "power_in"))
      (node (ref "U5") (pin "15") (pinfunction "VS_15") (pintype "power_in"))
      (node (ref "U6") (pin "15") (pinfunction "VS_15") (pintype "power_in"))
    )
    (net (code "55") (name "PWR_GND") (class "Default")
      (node (ref "C14") (pin "1") (pinfunction "1_1") (pintype "passive"))
      (node (ref "C16") (pin "2") (pinfunction "2_2") (pintype "passive"))
      (node (ref "C21") (pin "1") (pinfunction "1_1") (pintype "passive"))
      (node (ref "C22") (pin "2") (pinfunction "2_2") (pintype "passive"))
      (node (ref "C4") (pin "1") (pinfunction "1_1") (pintype "passive"))
      (node (ref "C7") (pin "1") (pinfunction "1_1") (pintype "passive"))
      (node (ref "C8") (pin "2") (pinfunction "2_2") (pintype "passive"))
      (node (ref "C9") (pin "2") (pinfunction "2_2") (pintype "passive"))
      (node (ref "D0") (pin "1") (pinfunction "1_1") (pintype "passive"))
      (node (ref "J1") (pin "1") (pinfunction "1_1") (pintype "passive"))
      (node (ref "J1") (pin "4") (pinfunction "4_4") (pintype "passive"))
      (node (ref "J1") (pin "5") (pinfunction "5_5") (pintype "passive"))
      (node (ref "J1") (pin "A1") (pinfunction "1_A1") (pintype "passive"))
      (node (ref "J1") (pin "A4") (pinfunction "4_A4") (pintype "passive"))
      (node (ref "J1") (pin "A5") (pinfunction "5_A5") (pintype "passive"))
      (node (ref "J13") (pin "3") (pinfunction "3_3") (pintype "passive"))
      (node (ref "J13") (pin "5") (pinfunction "5_5") (pintype "passive"))
      (node (ref "J13") (pin "A3") (pinfunction "3_A3") (pintype "passive"))
      (node (ref "J13") (pin "A5") (pinfunction "5_A5") (pintype "passive"))
      (node (ref "J15") (pin "3") (pinfunction "3_3") (pintype "passive"))
      (node (ref "J15") (pin "4") (pinfunction "4_4") (pintype "passive"))
      (node (ref "J15") (pin "7") (pinfunction "7_7") (pintype "passive"))
      (node (ref "J15") (pin "8") (pinfunction "8_8") (pintype "passive"))
      (node (ref "J15") (pin "A3") (pinfunction "3_A3") (pintype "passive"))
      (node (ref "J15") (pin "A4") (pinfunction "4_A4") (pintype "passive"))
      (node (ref "J15") (pin "A7") (pinfunction "7_A7") (pintype "passive"))
      (node (ref "J15") (pin "A8") (pinfunction "8_A8") (pintype "passive"))
      (node (ref "J9") (pin "1") (pinfunction "1_1") (pintype "passive"))
      (node (ref "J9") (pin "3") (pinfunction "3_3") (pintype "passive"))
      (node (ref "J9") (pin "5") (pinfunction "5_5") (pintype "passive"))
      (node (ref "MP1") (pin "1") (pinfunction "1_1") (pintype "passive"))
      (node (ref "MP2") (pin "1") (pinfunction "1_1") (pintype "passive"))
      (node (ref "MP3") (pin "1") (pinfunction "1_1") (pintype "passive"))
      (node (ref "MP4") (pin "1") (pinfunction "1_1") (pintype "passive"))
      (node (ref "RX1") (pin "1") (pinfunction "1_1") (pintype "passive"))
      (node (ref "RX2") (pin "2") (pinfunction "2_2") (pintype "passive"))
      (node (ref "RX3") (pin "1") (pinfunction "1_1") (pintype "passive"))
      (node (ref "RX4") (pin "2") (pinfunction "2_2") (pintype "passive"))
      (node (ref "RX5") (pin "2") (pinfunction "2_2") (pintype "passive"))
      (node (ref "RX6") (pin "2") (pinfunction "2_2") (pintype "passive"))
      (node (ref "RX7") (pin "1") (pinfunction "1_1") (pintype "passive"))
      (node (ref "RX8") (pin "1") (pinfunction "1_1") (pintype "passive"))
    )
    (net (code "56") (name "Q1") (class "Default")
      (node (ref "C7") (pin "2") (pinfunction "2_2") (pintype "passive"))
      (node (ref "D1") (pin "2") (pinfunction "+_2") (pintype "passive"))
      (node (ref "J13") (pin "2") (pinfunction "2_2") (pintype "passive"))
      (node (ref "J13") (pin "A2") (pinfunction "2_A2") (pintype "passive"))
      (node (ref "U2") (pin "10") (pinfunction "OUT1C_10") (pintype "output"))
      (node (ref "U2") (pin "8") (pinfunction "OUT1A_8") (pintype "output"))
      (node (ref "U2") (pin "9") (pinfunction "OUT1B_9") (pintype "output"))
    )
    (net (code "57") (name "Q1C") (class "Default")
      (node (ref "ESP32-J3") (pin "18") (pinfunction "18_18") (pintype "passive"))
      (node (ref "R13") (pin "1") (pinfunction "1_1") (pintype "passive"))
    )
    (net (code "58") (name "Q2") (class "Default")
      (node (ref "C8") (pin "1") (pinfunction "1_1") (pintype "passive"))
      (node (ref "D2") (pin "2") (pinfunction "+_2") (pintype "passive"))
      (node (ref "J13") (pin "1") (pinfunction "1_1") (pintype "passive"))
      (node (ref "J13") (pin "A1") (pinfunction "1_A1") (pintype "passive"))
      (node (ref "U2") (pin "12") (pinfunction "OUT0A_12") (pintype "output"))
      (node (ref "U2") (pin "13") (pinfunction "OUT0B_13") (pintype "output"))
      (node (ref "U2") (pin "14") (pinfunction "OUT0C_14") (pintype "output"))
    )
    (net (code "59") (name "Q2C") (class "Default")
      (node (ref "ESP32-J3") (pin "17") (pinfunction "17_17") (pintype "passive"))
      (node (ref "R15") (pin "2") (pinfunction "2_2") (pintype "passive"))
      (node (ref "R18") (pin "1") (pinfunction "1_1") (pintype "passive"))
    )
    (net (code "60") (name "Q3") (class "Default")
      (node (ref "C4") (pin "2") (pinfunction "2_2") (pintype "passive"))
      (node (ref "D3") (pin "2") (pinfunction "+_2") (pintype "passive"))
      (node (ref "J15") (pin "6") (pinfunction "6_6") (pintype "passive"))
      (node (ref "J15") (pin "A6") (pinfunction "6_A6") (pintype "passive"))
      (node (ref "U3") (pin "10") (pinfunction "OUT1C_10") (pintype "output"))
      (node (ref "U3") (pin "8") (pinfunction "OUT1A_8") (pintype "output"))
      (node (ref "U3") (pin "9") (pinfunction "OUT1B_9") (pintype "output"))
    )
    (net (code "61") (name "Q3C") (class "Default")
      (node (ref "ESP32-J3") (pin "9") (pinfunction "9_9") (pintype "passive"))
      (node (ref "R14") (pin "2") (pinfunction "2_2") (pintype "passive"))
      (node (ref "R4") (pin "1") (pinfunction "1_1") (pintype "passive"))
    )
    (net (code "62") (name "Q4") (class "Default")
      (node (ref "C9") (pin "1") (pinfunction "1_1") (pintype "passive"))
      (node (ref "D4") (pin "2") (pinfunction "+_2") (pintype "passive"))
      (node (ref "J15") (pin "5") (pinfunction "5_5") (pintype "passive"))
      (node (ref "J15") (pin "A5") (pinfunction "5_A5") (pintype "passive"))
      (node (ref "U3") (pin "12") (pinfunction "OUT0A_12") (pintype "output"))
      (node (ref "U3") (pin "13") (pinfunction "OUT0B_13") (pintype "output"))
      (node (ref "U3") (pin "14") (pinfunction "OUT0C_14") (pintype "output"))
    )
    (net (code "63") (name "Q4C") (class "Default")
      (node (ref "ESP32-J3") (pin "8") (pinfunction "8_8") (pintype "passive"))
      (node (ref "R2") (pin "1") (pinfunction "1_1") (pintype "passive"))
    )
    (net (code "64") (name "Q5") (class "Default")
      (node (ref "C14") (pin "2") (pinfunction "2_2") (pintype "passive"))
      (node (ref "D8") (pin "2") (pinfunction "+_2") (pintype "passive"))
      (node (ref "J15") (pin "2") (pinfunction "2_2") (pintype "passive"))
      (node (ref "J15") (pin "A2") (pinfunction "2_A2") (pintype "passive"))
      (node (ref "U5") (pin "10") (pinfunction "OUT1C_10") (pintype "output"))
      (node (ref "U5") (pin "8") (pinfunction "OUT1A_8") (pintype "output"))
      (node (ref "U5") (pin "9") (pinfunction "OUT1B_9") (pintype "output"))
    )
    (net (code "65") (name "Q5C") (class "Default")
      (node (ref "ESP32-J3") (pin "7") (pinfunction "7_7") (pintype "passive"))
      (node (ref "R6") (pin "1") (pinfunction "1_1") (pintype "passive"))
    )
    (net (code "66") (name "Q6") (class "Default")
      (node (ref "C16") (pin "1") (pinfunction "1_1") (pintype "passive"))
      (node (ref "D7") (pin "2") (pinfunction "+_2") (pintype "passive"))
      (node (ref "J15") (pin "1") (pinfunction "1_1") (pintype "passive"))
      (node (ref "J15") (pin "A1") (pinfunction "1_A1") (pintype "passive"))
      (node (ref "U5") (pin "12") (pinfunction "OUT0A_12") (pintype "output"))
      (node (ref "U5") (pin "13") (pinfunction "OUT0B_13") (pintype "output"))
      (node (ref "U5") (pin "14") (pinfunction "OUT0C_14") (pintype "output"))
    )
    (net (code "67") (name "Q6C") (class "Default")
      (node (ref "ESP32-J3") (pin "6") (pinfunction "6_6") (pintype "passive"))
      (node (ref "R5") (pin "1") (pinfunction "1_1") (pintype "passive"))
    )
    (net (code "68") (name "Q7") (class "Default")
      (node (ref "C21") (pin "2") (pinfunction "2_2") (pintype "passive"))
      (node (ref "D10") (pin "2") (pinfunction "+_2") (pintype "passive"))
      (node (ref "J1") (pin "3") (pinfunction "3_3") (pintype "passive"))
      (node (ref "J1") (pin "A3") (pinfunction "3_A3") (pintype "passive"))
      (node (ref "U6") (pin "10") (pinfunction "OUT1C_10") (pintype "output"))
      (node (ref "U6") (pin "8") (pinfunction "OUT1A_8") (pintype "output"))
      (node (ref "U6") (pin "9") (pinfunction "OUT1B_9") (pintype "output"))
    )
    (net (code "69") (name "Q7C") (class "Default")
      (node (ref "ESP32-J3") (pin "4") (pinfunction "4_4") (pintype "passive"))
      (node (ref "R11") (pin "1") (pinfunction "1_1") (pintype "passive"))
    )
    (net (code "70") (name "Q8") (class "Default")
      (node (ref "C22") (pin "1") (pinfunction "1_1") (pintype "passive"))
      (node (ref "D9") (pin "2") (pinfunction "+_2") (pintype "passive"))
      (node (ref "J1") (pin "2") (pinfunction "2_2") (pintype "passive"))
      (node (ref "J1") (pin "A2") (pinfunction "2_A2") (pintype "passive"))
      (node (ref "U6") (pin "12") (pinfunction "OUT0A_12") (pintype "output"))
      (node (ref "U6") (pin "13") (pinfunction "OUT0B_13") (pintype "output"))
      (node (ref "U6") (pin "14") (pinfunction "OUT0C_14") (pintype "output"))
    )
    (net (code "71") (name "Q8C") (class "Default")
      (node (ref "ESP32-J3") (pin "5") (pinfunction "5_5") (pintype "passive"))
      (node (ref "R9") (pin "1") (pinfunction "1_1") (pintype "passive"))
    )
    (net (code "72") (name "RESET") (class "Default")
      (node (ref "ESP32-J1") (pin "3") (pinfunction "3_3") (pintype "passive"))
    )
    (net (code "73") (name "RST0") (class "Default")
      (node (ref "ESP32-J1") (pin "9") (pinfunction "9_9") (pintype "passive"))
      (node (ref "W1-J2") (pin "3") (pinfunction "3_3") (pintype "passive"))
    )
    (net (code "74") (name "RST1") (class "Default")
      (node (ref "ESP32-J3") (pin "10") (pinfunction "10_10") (pintype "passive"))
      (node (ref "W2-J2") (pin "3") (pinfunction "3_3") (pintype "passive"))
    )
    (net (code "75") (name "SCLK") (class "Default")
      (node (ref "ESP32-J1") (pin "16") (pinfunction "16_16") (pintype "passive"))
      (node (ref "W1-J1") (pin "5") (pinfunction "5_5") (pintype "passive"))
      (node (ref "W2-J1") (pin "5") (pinfunction "5_5") (pintype "passive"))
    )
    (net (code "76") (name "unconnected-(ESP32-J1-Pad8)") (class "Default")
      (node (ref "ESP32-J1") (pin "8") (pinfunction "8_8") (pintype "passive"))
    )
    (net (code "77") (name "unconnected-(ESP32-J3-Pad2)") (class "Default")
      (node (ref "ESP32-J3") (pin "2") (pinfunction "2_2") (pintype "passive"))
    )
    (net (code "78") (name "unconnected-(ESP32-J3-Pad3)") (class "Default")
      (node (ref "ESP32-J3") (pin "3") (pinfunction "3_3") (pintype "passive"))
    )
    (net (code "79") (name "unconnected-(ESP32-J3-Pad11)") (class "Default")
      (node (ref "ESP32-J3") (pin "11") (pinfunction "11_11") (pintype "passive"))
    )
    (net (code "80") (name "unconnected-(ESP32-J3-Pad12)") (class "Default")
      (node (ref "ESP32-J3") (pin "12") (pinfunction "12_12") (pintype "passive"))
    )
    (net (code "81") (name "unconnected-(ESP32-J3-Pad13)") (class "Default")
      (node (ref "ESP32-J3") (pin "13") (pinfunction "13_13") (pintype "passive"))
    )
    (net (code "82") (name "unconnected-(ESP32-J3-Pad19)") (class "Default")
      (node (ref "ESP32-J3") (pin "19") (pinfunction "19_19") (pintype "passive"))
    )
    (net (code "83") (name "unconnected-(ESP32-J3-Pad20)") (class "Default")
      (node (ref "ESP32-J3") (pin "20") (pinfunction "20_20") (pintype "passive"))
    )
    (net (code "84") (name "unconnected-(U2-DEN-Pad3)") (class "Default")
      (node (ref "U2") (pin "3") (pinfunction "DEN_3") (pintype "input"))
    )
    (net (code "85") (name "unconnected-(U2-DSEL-Pad5)") (class "Default")
      (node (ref "U2") (pin "5") (pinfunction "DSEL_5") (pintype "input"))
    )
    (net (code "86") (name "unconnected-(U2-IS-Pad4)") (class "Default")
      (node (ref "U2") (pin "4") (pinfunction "IS_4") (pintype "output"))
    )
    (net (code "87") (name "unconnected-(U2-NC1-Pad7)") (class "Default")
      (node (ref "U2") (pin "7") (pinfunction "NC1_7") (pintype "passive"))
    )
    (net (code "88") (name "unconnected-(U2-NC2-Pad11)") (class "Default")
      (node (ref "U2") (pin "11") (pinfunction "NC2_11") (pintype "passive"))
    )
    (net (code "89") (name "unconnected-(U3-DEN-Pad3)") (class "Default")
      (node (ref "U3") (pin "3") (pinfunction "DEN_3") (pintype "input"))
    )
    (net (code "90") (name "unconnected-(U3-DSEL-Pad5)") (class "Default")
      (node (ref "U3") (pin "5") (pinfunction "DSEL_5") (pintype "input"))
    )
    (net (code "91") (name "unconnected-(U3-IS-Pad4)") (class "Default")
      (node (ref "U3") (pin "4") (pinfunction "IS_4") (pintype "output"))
    )
    (net (code "92") (name "unconnected-(U3-NC1-Pad7)") (class "Default")
      (node (ref "U3") (pin "7") (pinfunction "NC1_7") (pintype "passive"))
    )
    (net (code "93") (name "unconnected-(U3-NC2-Pad11)") (class "Default")
      (node (ref "U3") (pin "11") (pinfunction "NC2_11") (pintype "passive"))
    )
    (net (code "94") (name "unconnected-(U5-DEN-Pad3)") (class "Default")
      (node (ref "U5") (pin "3") (pinfunction "DEN_3") (pintype "input"))
    )
    (net (code "95") (name "unconnected-(U5-DSEL-Pad5)") (class "Default")
      (node (ref "U5") (pin "5") (pinfunction "DSEL_5") (pintype "input"))
    )
    (net (code "96") (name "unconnected-(U5-IS-Pad4)") (class "Default")
      (node (ref "U5") (pin "4") (pinfunction "IS_4") (pintype "output"))
    )
    (net (code "97") (name "unconnected-(U5-NC1-Pad7)") (class "Default")
      (node (ref "U5") (pin "7") (pinfunction "NC1_7") (pintype "passive"))
    )
    (net (code "98") (name "unconnected-(U5-NC2-Pad11)") (class "Default")
      (node (ref "U5") (pin "11") (pinfunction "NC2_11") (pintype "passive"))
    )
    (net (code "99") (name "unconnected-(U6-DEN-Pad3)") (class "Default")
      (node (ref "U6") (pin "3") (pinfunction "DEN_3") (pintype "input"))
    )
    (net (code "100") (name "unconnected-(U6-DSEL-Pad5)") (class "Default")
      (node (ref "U6") (pin "5") (pinfunction "DSEL_5") (pintype "input"))
    )
    (net (code "101") (name "unconnected-(U6-IS-Pad4)") (class "Default")
      (node (ref "U6") (pin "4") (pinfunction "IS_4") (pintype "output"))
    )
    (net (code "102") (name "unconnected-(U6-NC1-Pad7)") (class "Default")
      (node (ref "U6") (pin "7") (pinfunction "NC1_7") (pintype "passive"))
    )
    (net (code "103") (name "unconnected-(U6-NC2-Pad11)") (class "Default")
      (node (ref "U6") (pin "11") (pinfunction "NC2_11") (pintype "passive"))
    )
    (net (code "104") (name "unconnected-(W1-J2-Pad2)") (class "Default")
      (node (ref "W1-J2") (pin "2") (pinfunction "2_2") (pintype "passive"))
    )
    (net (code "105") (name "unconnected-(W1-J2-Pad4)") (class "Default")
      (node (ref "W1-J2") (pin "4") (pinfunction "4_4") (pintype "passive"))
    )
    (net (code "106") (name "unconnected-(W2-J2-Pad2)") (class "Default")
      (node (ref "W2-J2") (pin "2") (pinfunction "2_2") (pintype "passive"))
    )
    (net (code "107") (name "unconnected-(W2-J2-Pad4)") (class "Default")
      (node (ref "W2-J2") (pin "4") (pinfunction "4_4") (pintype "passive"))
    )
  )
)
